# rekick2015-003.net
KiCad netlist of a schematic drawn in EAGLE
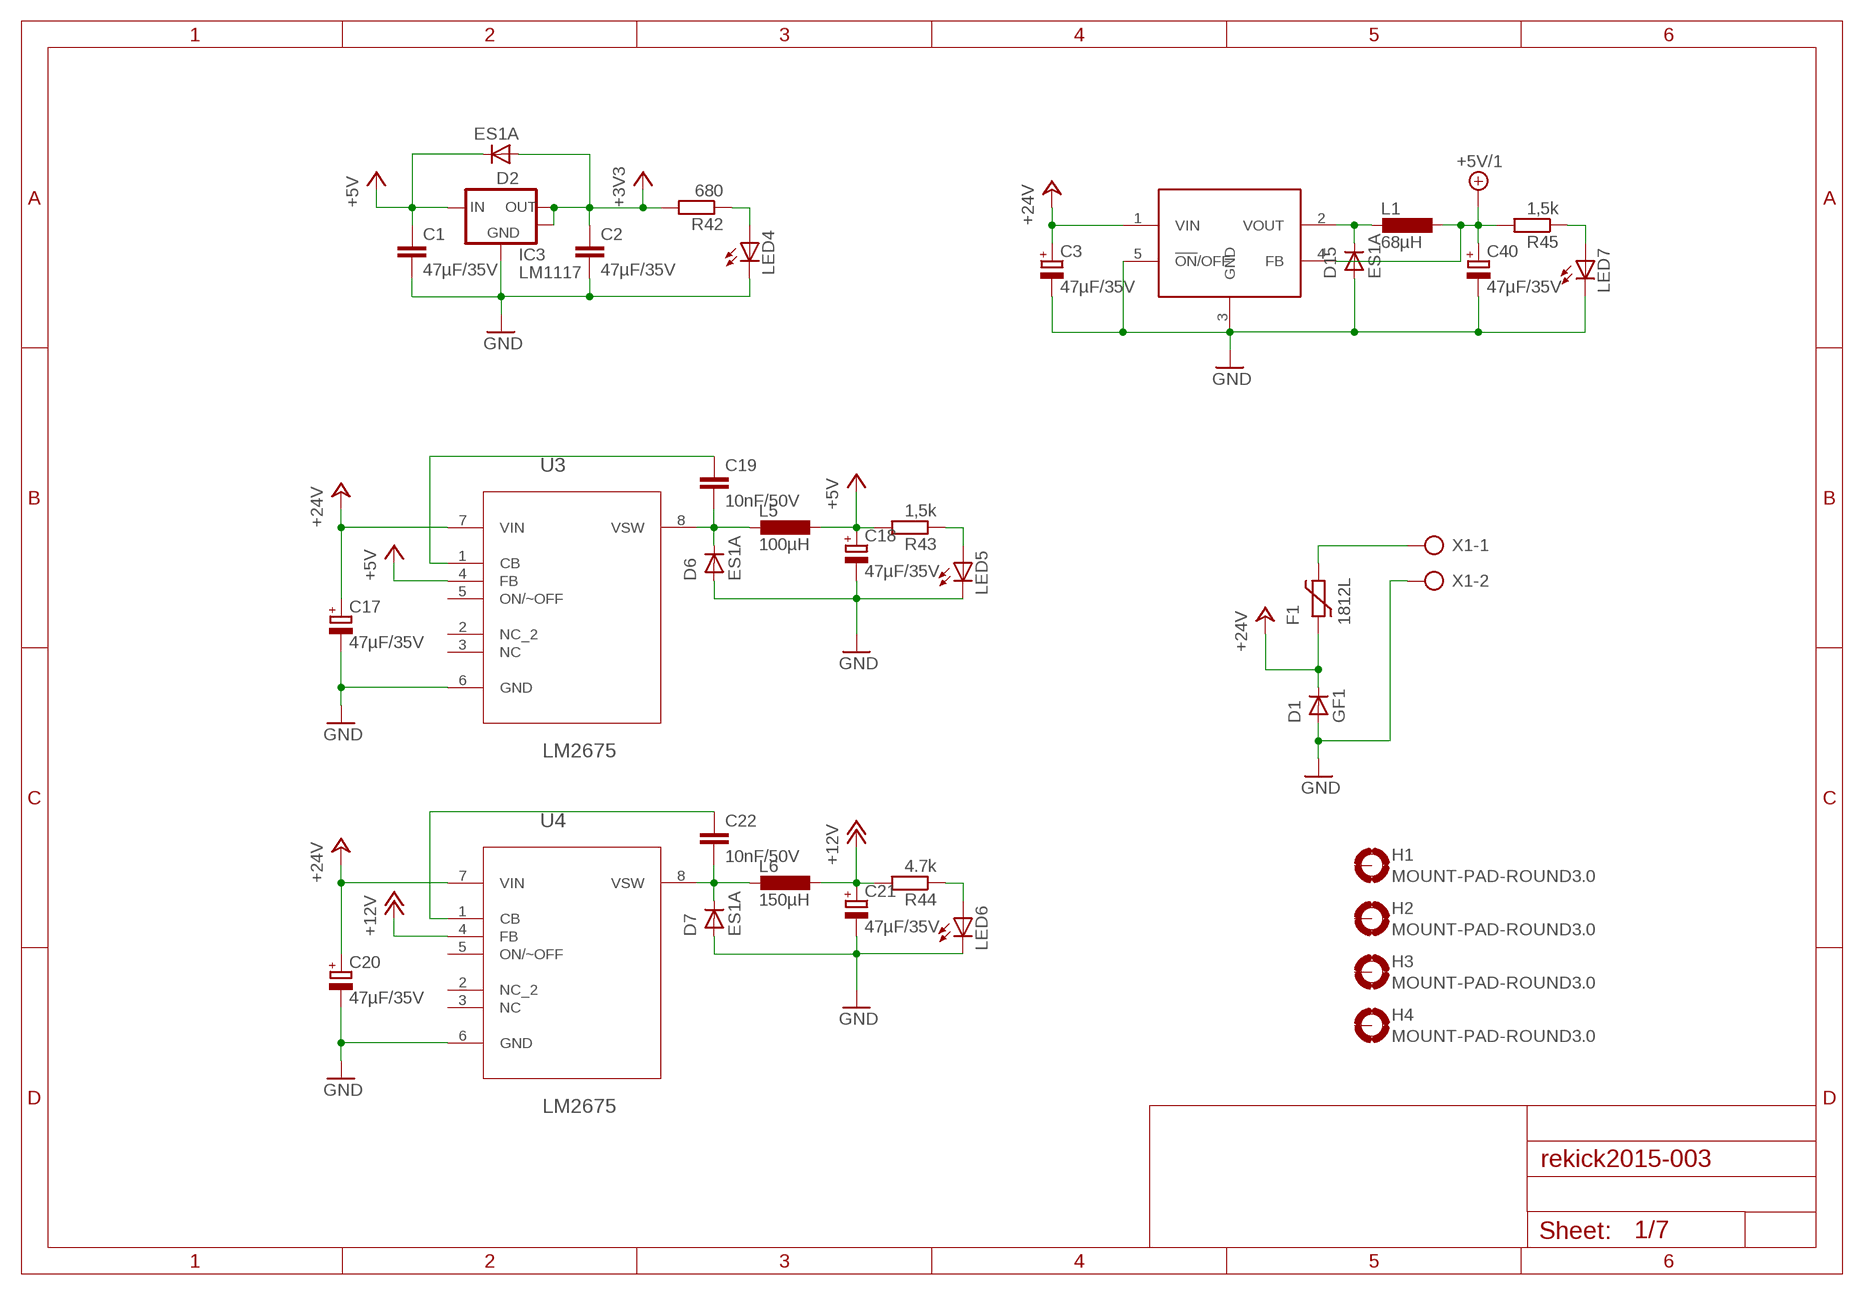
[diagram p0: schematic, sheet 1]
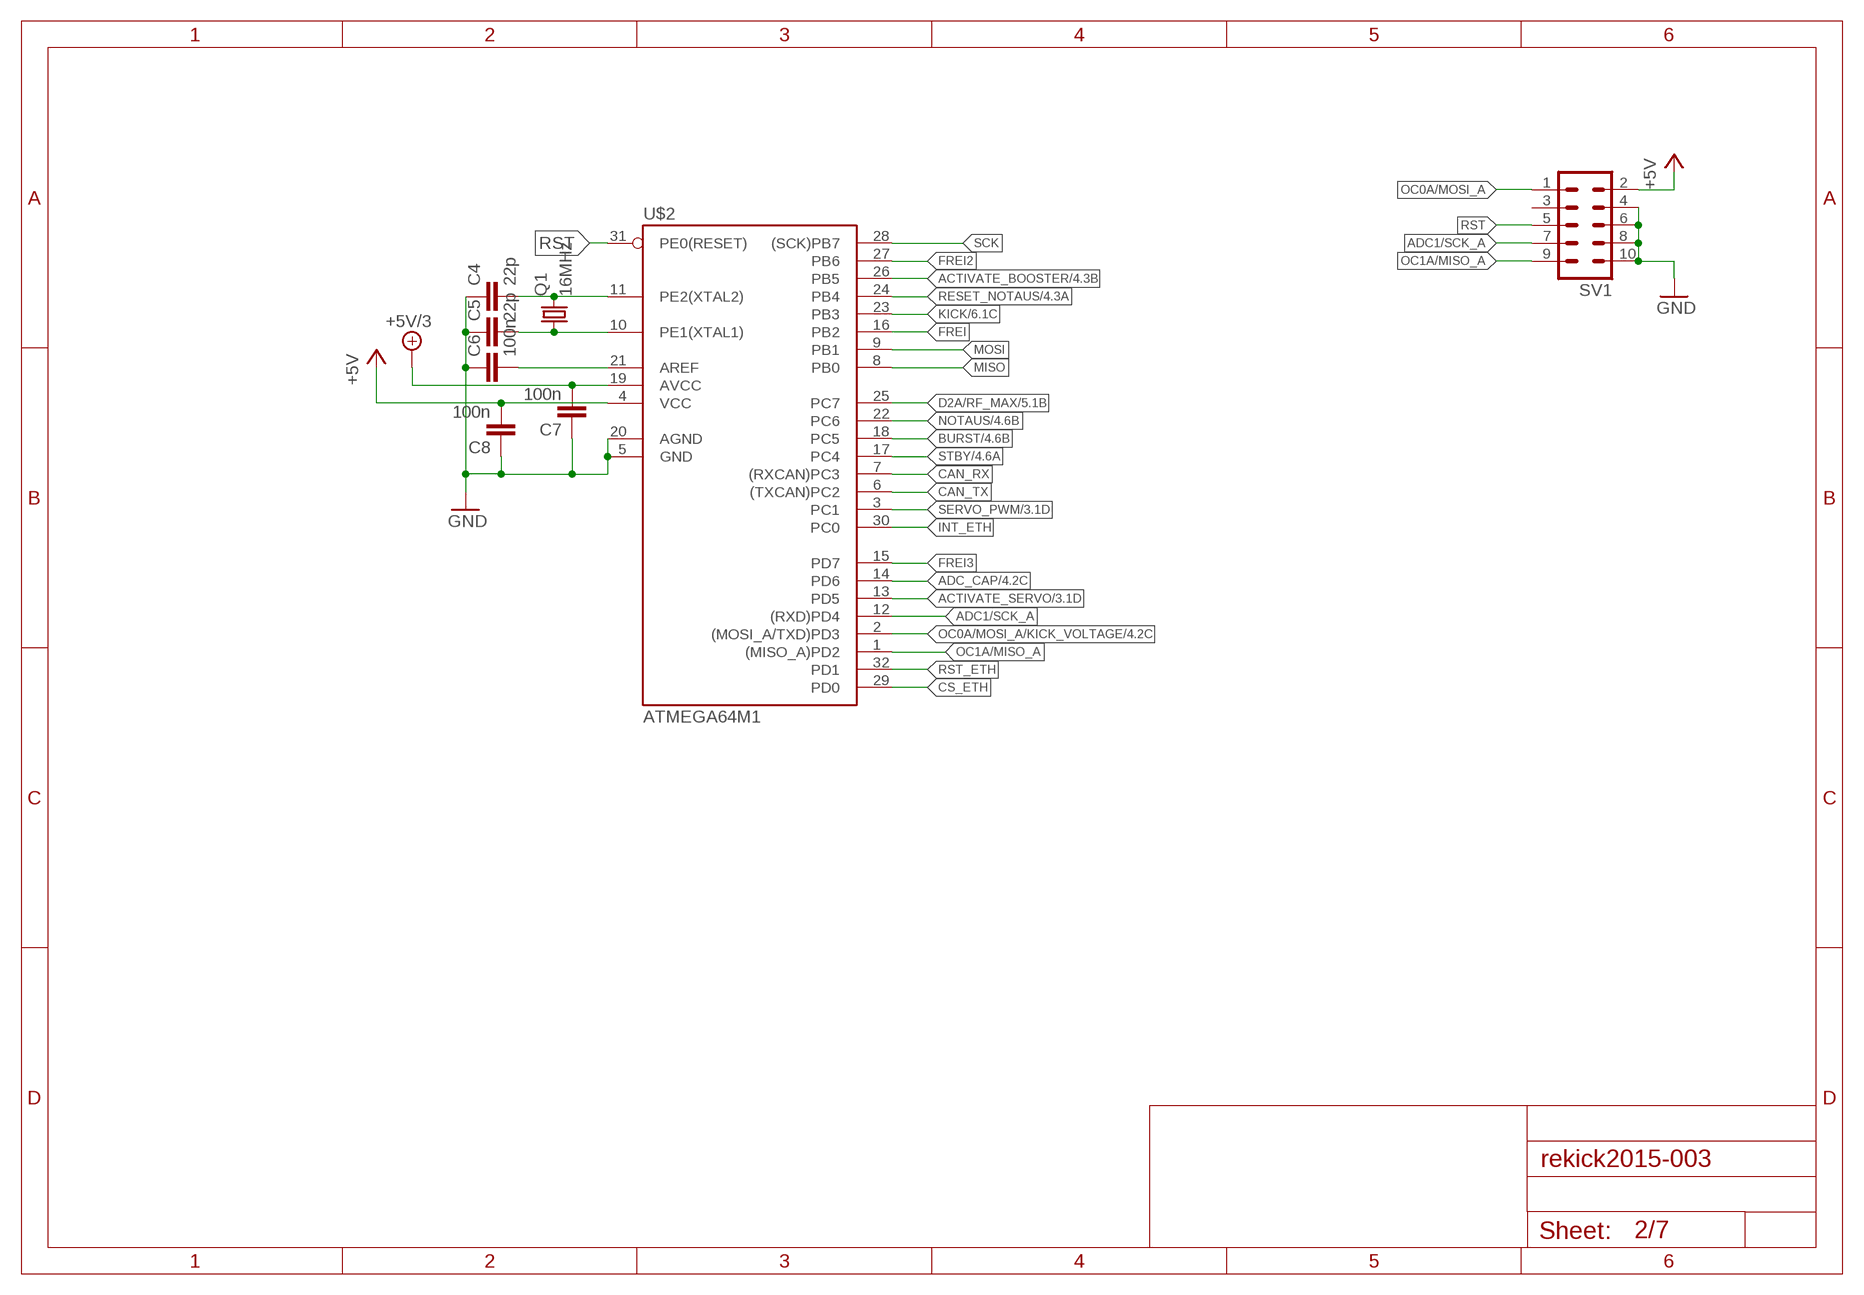
[diagram p1: schematic, sheet 2]
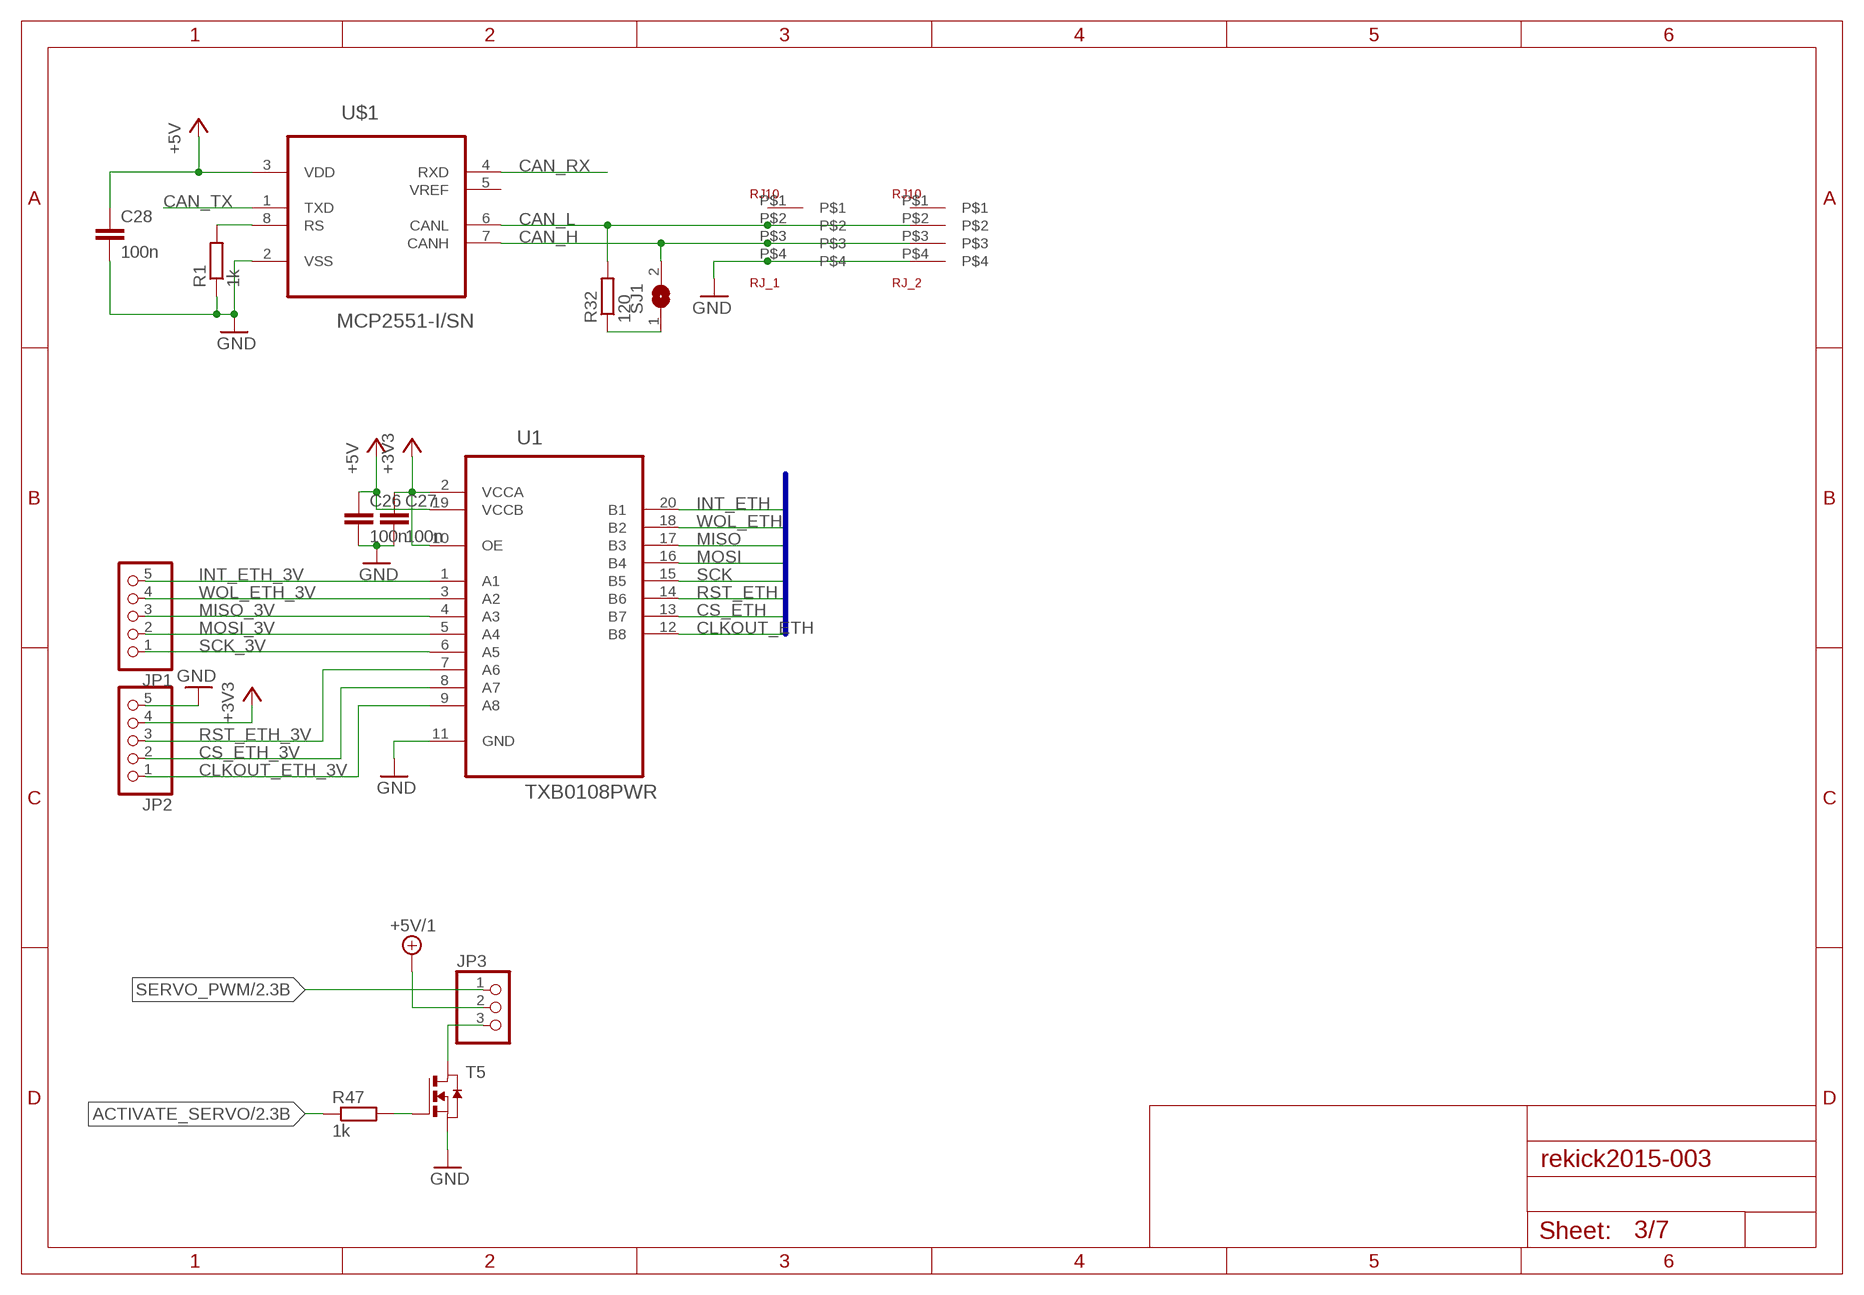
[diagram p2: schematic, sheet 3]
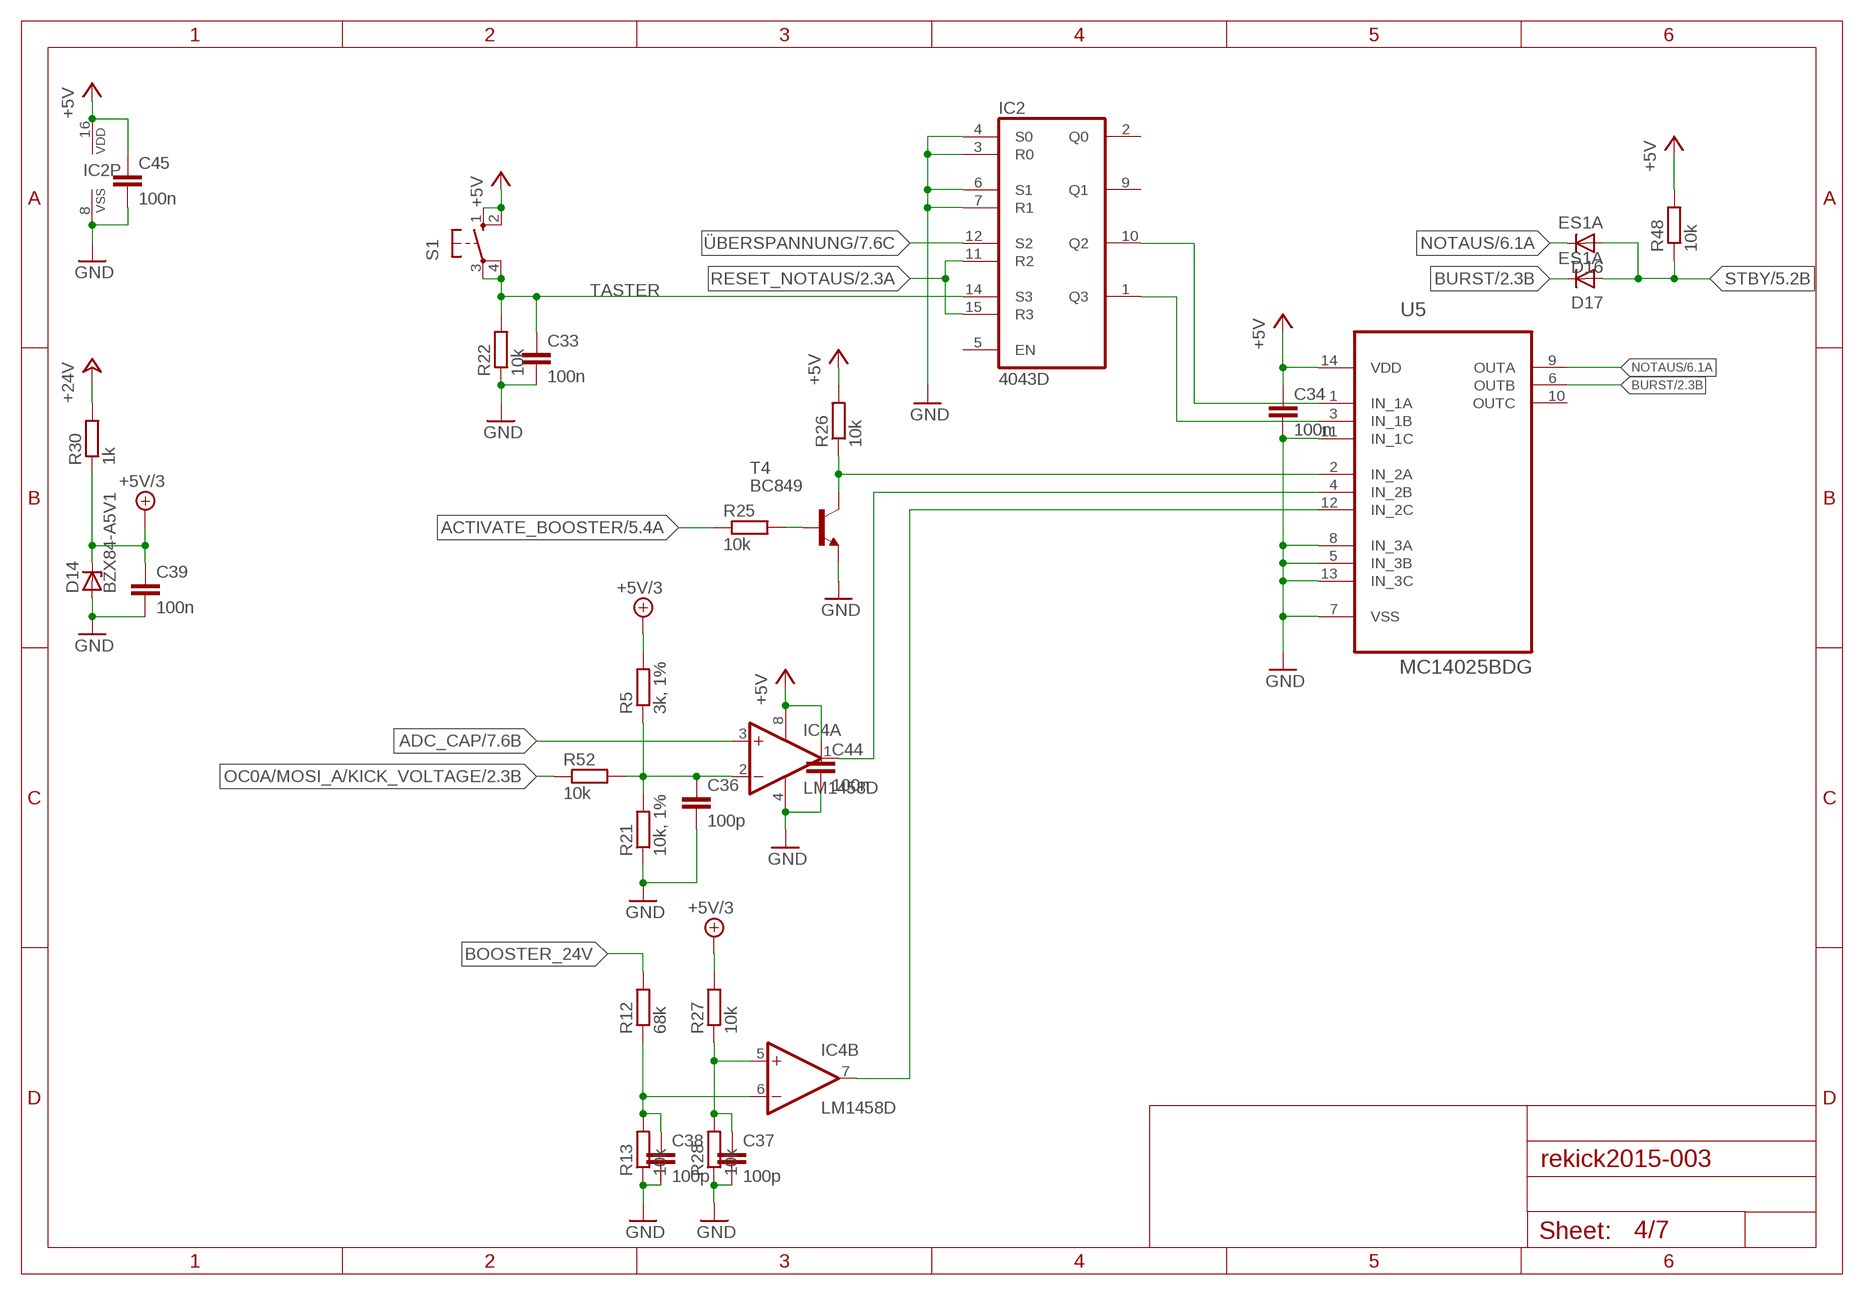
[diagram p3: schematic, sheet 4]
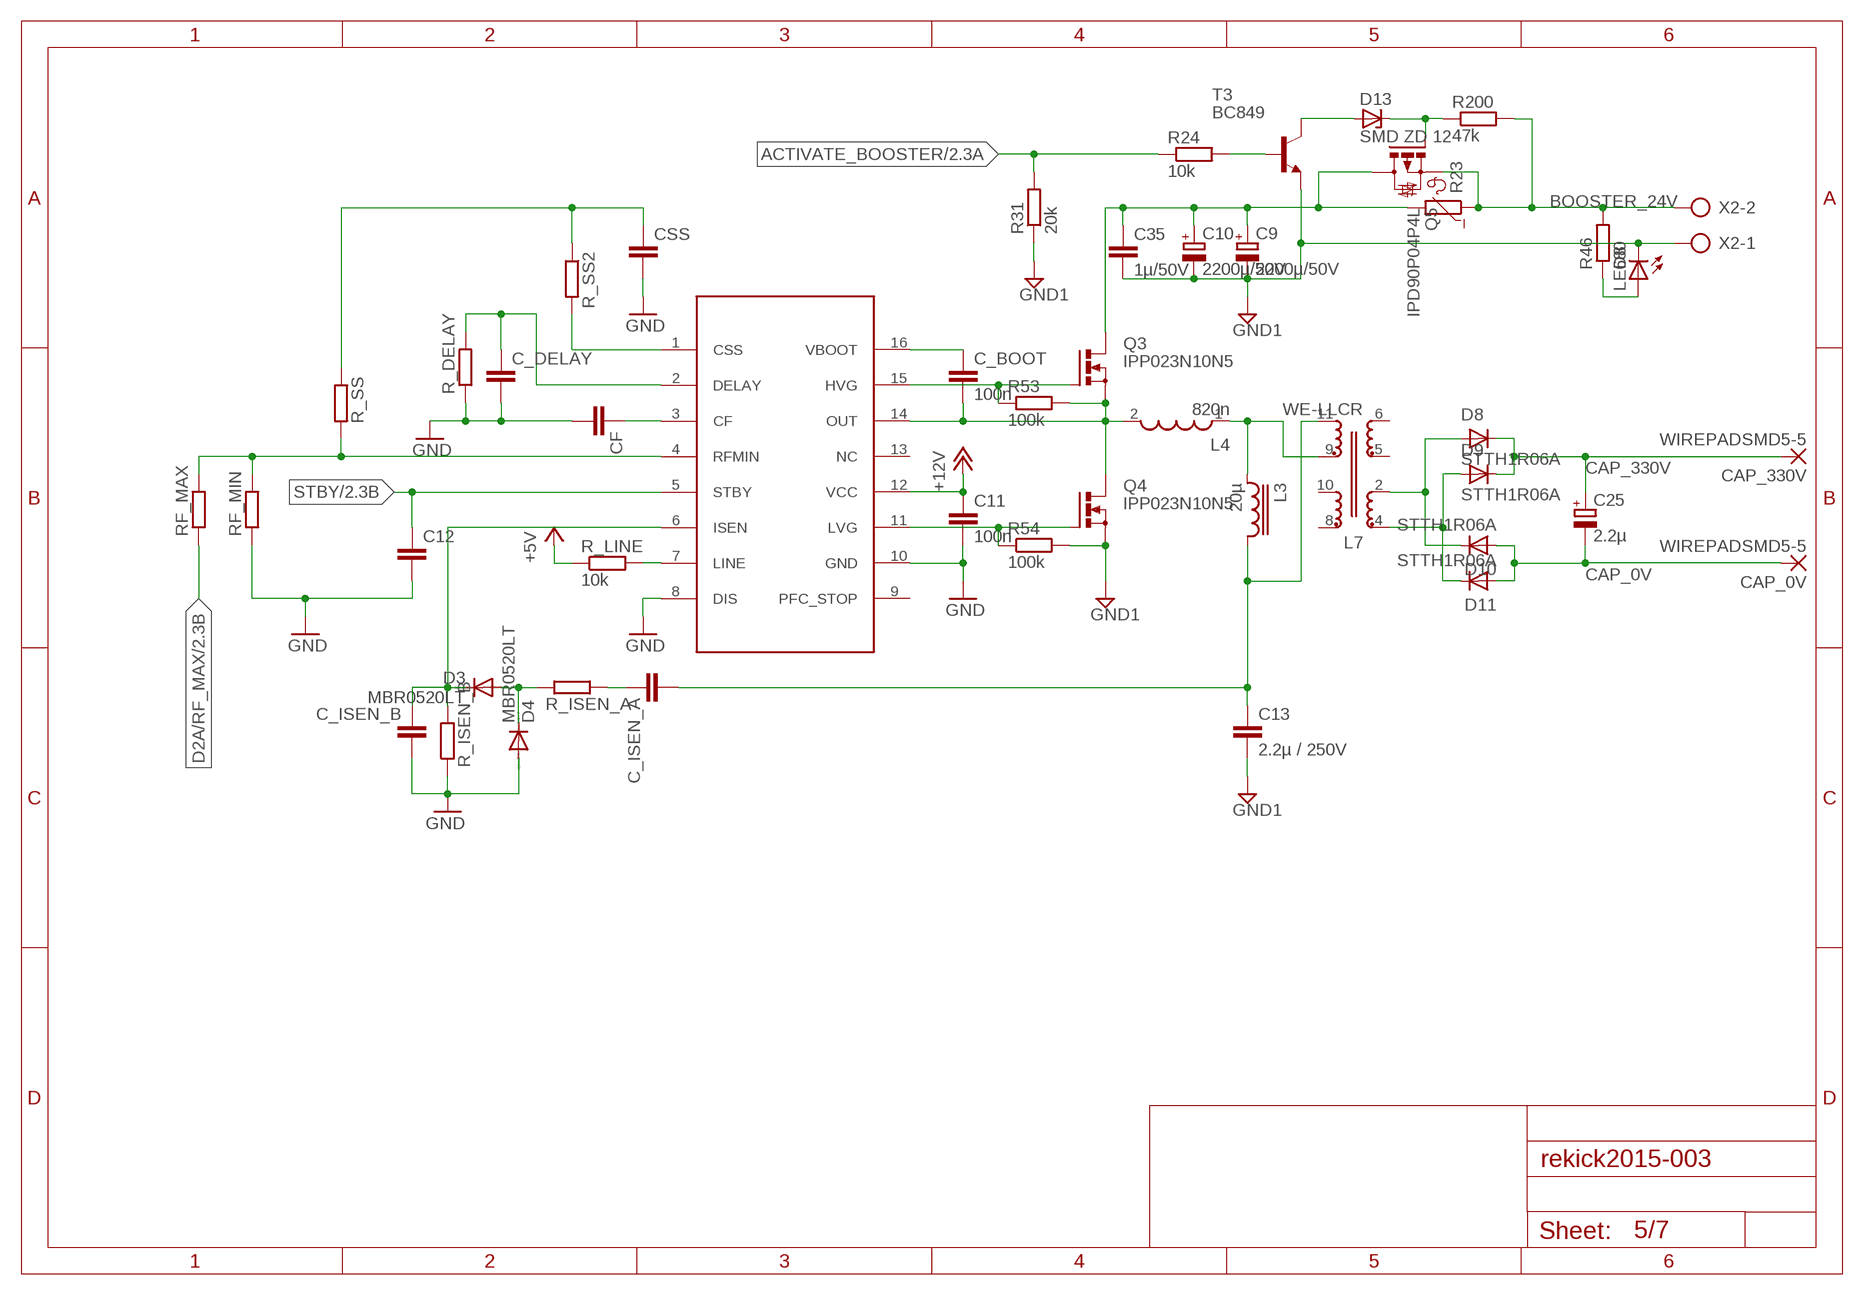
[diagram p4: schematic, sheet 5]
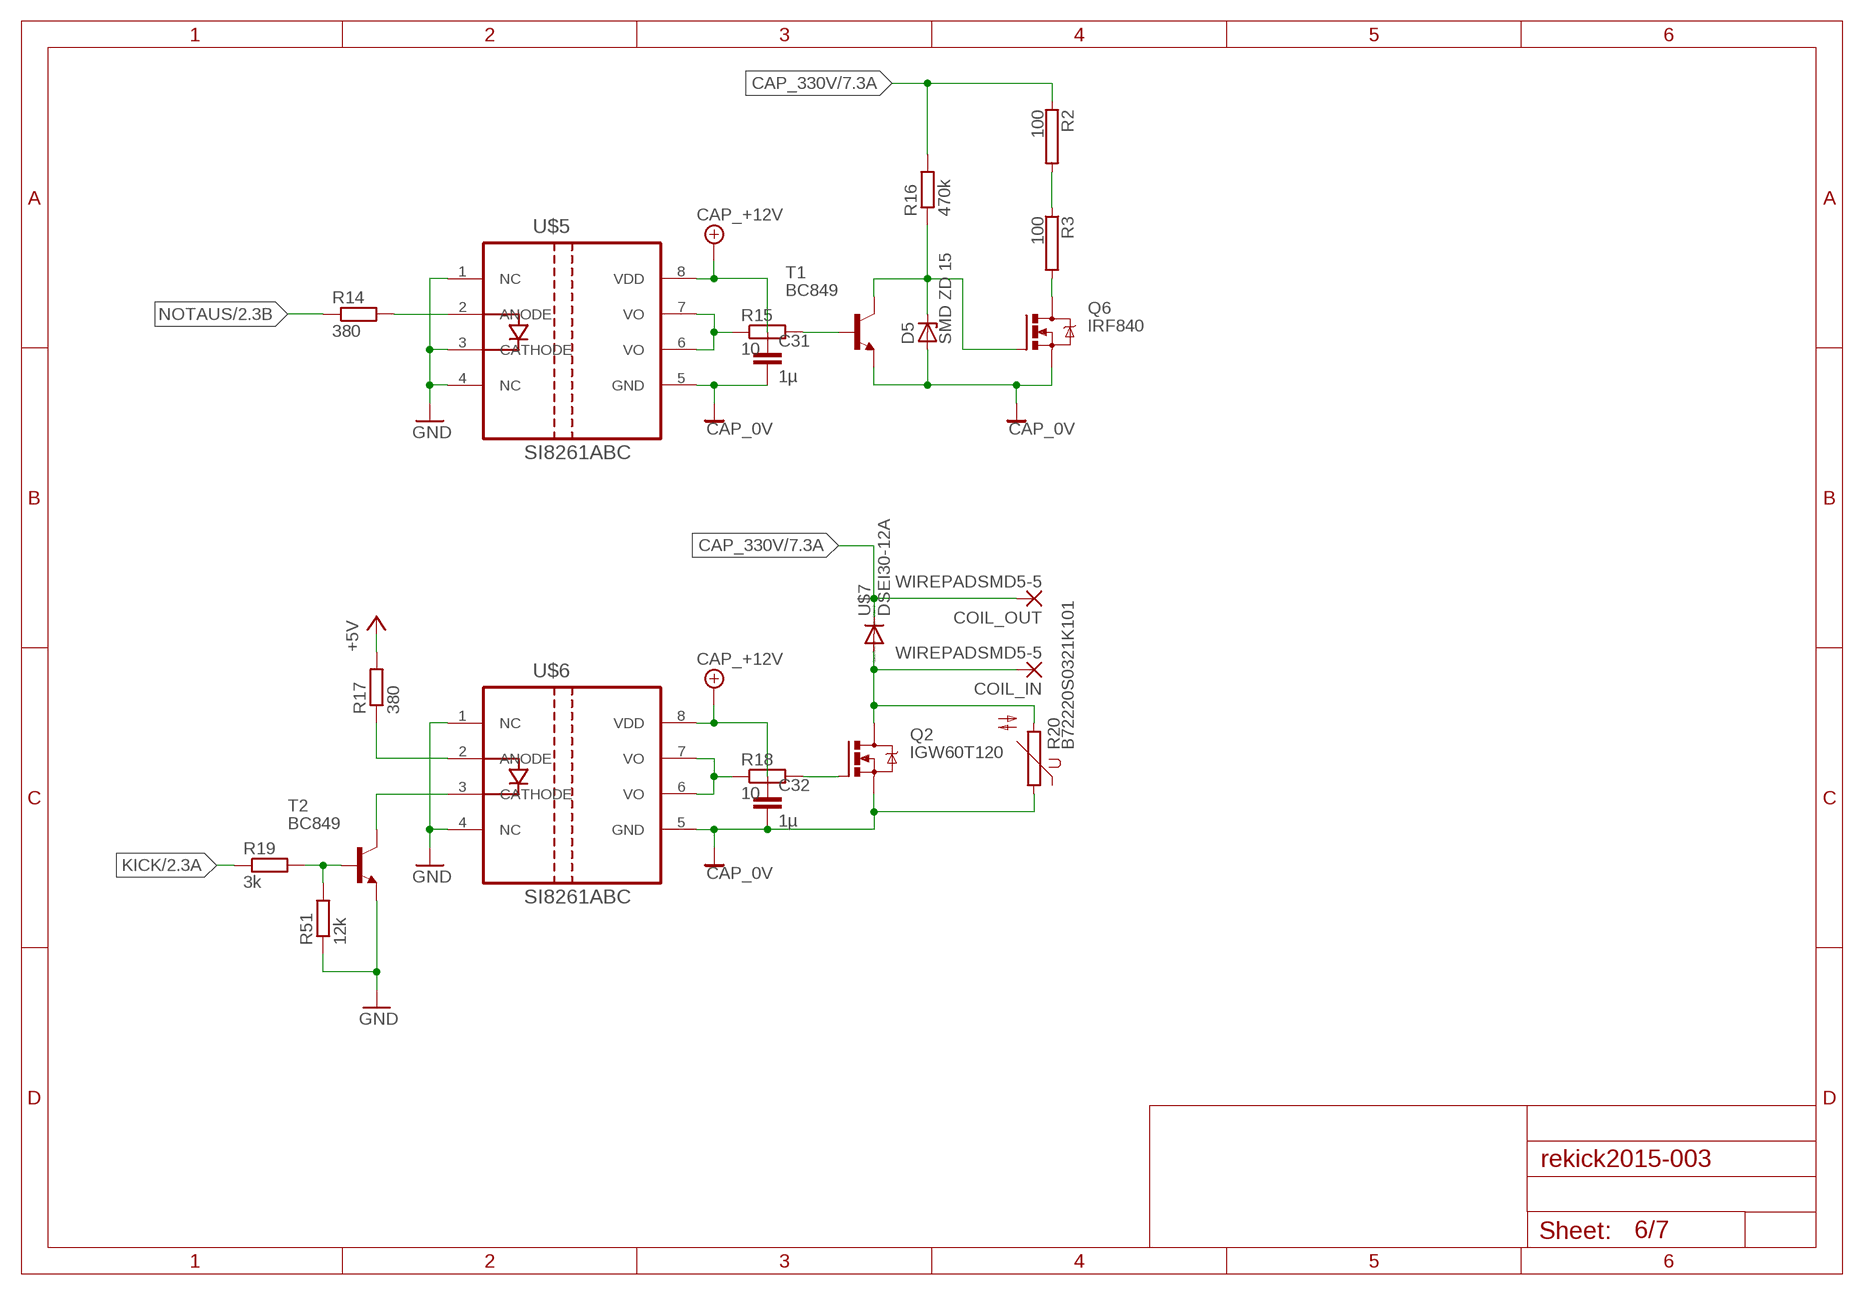
[diagram p5: schematic, sheet 6]
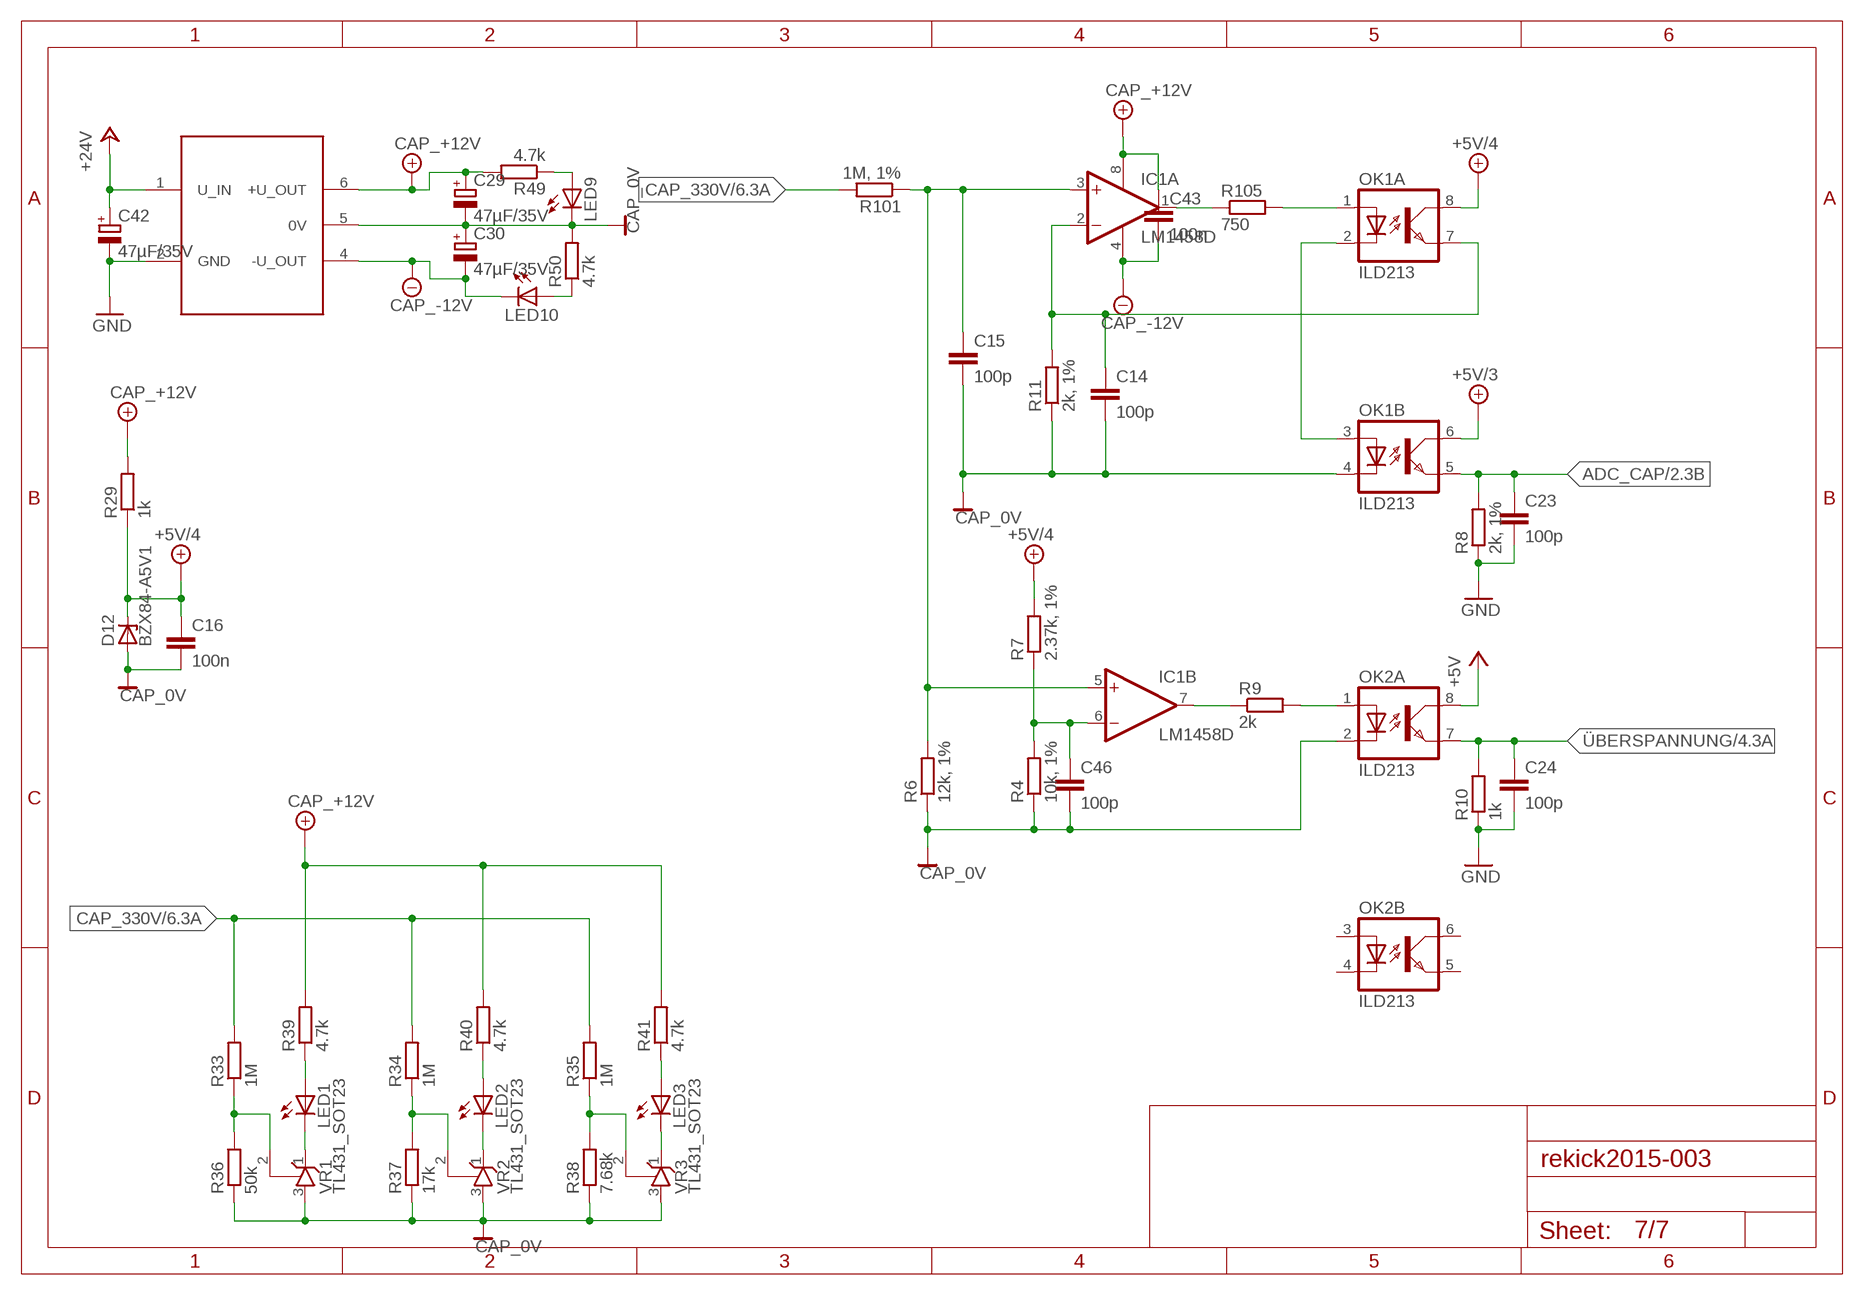
[diagram p6: schematic, sheet 7]

(export (version "E")
  (design (tool "Eeschema 10.0.6"))
  (components
    (comp (ref "C31")
      (value "1µ")
      (footprint "eagle-import:C0603")
      (libsource (lib "eagle-import") (part "C-EUC0603"))
    )
    (comp (ref "C32")
      (value "1µ")
      (footprint "eagle-import:C0603")
      (libsource (lib "eagle-import") (part "C-EUC0603"))
    )
    (comp (ref "COIL_IN")
      (value "WIREPADSMD5-5")
      (footprint "eagle-import:5-5")
      (libsource (lib "eagle-import") (part "WIREPADSMD5-5"))
    )
    (comp (ref "COIL_OUT")
      (value "WIREPADSMD5-5")
      (footprint "eagle-import:5-5")
      (libsource (lib "eagle-import") (part "WIREPADSMD5-5"))
    )
    (comp (ref "D5")
      (value "SMD ZD 15")
      (footprint "eagle-import:TO236")
      (libsource (lib "eagle-import") (part "BZX84CSMD"))
    )
    (comp (ref "Q2")
      (value "IGW60T120")
      (footprint "eagle-import:TO247BV")
      (libsource (lib "eagle-import") (part "IRFPC40"))
    )
    (comp (ref "Q6")
      (value "IRF840")
      (footprint "eagle-import:TO220BV")
      (libsource (lib "eagle-import") (part "IRF740"))
    )
    (comp (ref "R2")
      (value "100")
      (footprint "eagle-import:HS25")
      (libsource (lib "eagle-import") (part "RHS25"))
    )
    (comp (ref "R3")
      (value "100")
      (footprint "eagle-import:HS25")
      (libsource (lib "eagle-import") (part "RHS25"))
    )
    (comp (ref "R14")
      (value "380")
      (footprint "eagle-import:R0805")
      (libsource (lib "eagle-import") (part "R-EU_R0805"))
    )
    (comp (ref "R15")
      (value "10")
      (footprint "eagle-import:R0805")
      (libsource (lib "eagle-import") (part "R-EU_R0805"))
    )
    (comp (ref "R16")
      (value "470k")
      (footprint "eagle-import:0207_15")
      (libsource (lib "eagle-import") (part "R-EU_0207/15"))
    )
    (comp (ref "R17")
      (value "380")
      (footprint "eagle-import:R0805")
      (libsource (lib "eagle-import") (part "R-EU_R0805"))
    )
    (comp (ref "R18")
      (value "10")
      (footprint "eagle-import:R0805")
      (libsource (lib "eagle-import") (part "R-EU_R0805"))
    )
    (comp (ref "R19")
      (value "3k")
      (footprint "eagle-import:R0805")
      (libsource (lib "eagle-import") (part "R-EU_R0805"))
    )
    (comp (ref "R20")
      (value "B72220S0321K101")
      (footprint "eagle-import:S20K320")
      (libsource (lib "eagle-import") (part "S20K320"))
    )
    (comp (ref "R51")
      (value "12k")
      (footprint "eagle-import:R0805")
      (libsource (lib "eagle-import") (part "R-EU_R0805"))
    )
    (comp (ref "T1")
      (value "BC849")
      (footprint "eagle-import:SOT23")
      (libsource (lib "eagle-import") (part "BC849"))
    )
    (comp (ref "T2")
      (value "BC849")
      (footprint "eagle-import:SOT23")
      (libsource (lib "eagle-import") (part "BC849"))
    )
    (comp (ref "U$5")
      (value "SI8261ABC")
      (footprint "eagle-import:SOIC-8")
      (libsource (lib "eagle-import") (part "SI8261ABC"))
    )
    (comp (ref "U$6")
      (value "SI8261ABC")
      (footprint "eagle-import:SOIC-8")
      (libsource (lib "eagle-import") (part "SI8261ABC"))
    )
    (comp (ref "U$7")
      (value "DSEI30-12A")
      (footprint "eagle-import:TO247AD")
      (libsource (lib "eagle-import") (part "DSEI30-12A"))
    )
    (comp (ref "C33")
      (value "100n")
      (footprint "eagle-import:C0603")
      (libsource (lib "eagle-import") (part "C-EUC0603"))
    )
    (comp (ref "C34")
      (value "100n")
      (footprint "eagle-import:C0603")
      (libsource (lib "eagle-import") (part "C-EUC0603"))
    )
    (comp (ref "C36")
      (value "100p")
      (footprint "eagle-import:C0603")
      (libsource (lib "eagle-import") (part "C-EUC0603"))
    )
    (comp (ref "C37")
      (value "100p")
      (footprint "eagle-import:C0603")
      (libsource (lib "eagle-import") (part "C-EUC0603"))
    )
    (comp (ref "C38")
      (value "100p")
      (footprint "eagle-import:C0603")
      (libsource (lib "eagle-import") (part "C-EUC0603"))
    )
    (comp (ref "C39")
      (value "100n")
      (footprint "eagle-import:C0603")
      (libsource (lib "eagle-import") (part "C-EUC0603"))
    )
    (comp (ref "C44")
      (value "100n")
      (footprint "eagle-import:C0603")
      (libsource (lib "eagle-import") (part "C-EUC0603"))
    )
    (comp (ref "C45")
      (value "100n")
      (footprint "eagle-import:C0603")
      (libsource (lib "eagle-import") (part "C-EUC0603"))
    )
    (comp (ref "D14")
      (value "BZX84-A5V1")
      (footprint "eagle-import:TO236")
      (libsource (lib "eagle-import") (part "BZX84CSMD"))
    )
    (comp (ref "D16")
      (value "ES1A")
      (footprint "eagle-import:SMA-DO214AC")
      (libsource (lib "eagle-import") (part "GF1"))
    )
    (comp (ref "D17")
      (value "ES1A")
      (footprint "eagle-import:SMA-DO214AC")
      (libsource (lib "eagle-import") (part "GF1"))
    )
    (comp (ref "IC2")
      (value "4043D")
      (footprint "eagle-import:SO16")
      (libsource (lib "eagle-import") (part "4043D"))
    )
    (comp (ref "IC4")
      (value "LM1458D")
      (footprint "eagle-import:SO08")
      (libsource (lib "eagle-import") (part "1458DLM"))
    )
    (comp (ref "R5")
      (value "3k, 1%")
      (footprint "eagle-import:R0805")
      (libsource (lib "eagle-import") (part "R-EU_R0805"))
    )
    (comp (ref "R12")
      (value "68k")
      (footprint "eagle-import:R0805")
      (libsource (lib "eagle-import") (part "R-EU_R0805"))
    )
    (comp (ref "R13")
      (value "10k")
      (footprint "eagle-import:R0805")
      (libsource (lib "eagle-import") (part "R-EU_R0805"))
    )
    (comp (ref "R21")
      (value "10k, 1%")
      (footprint "eagle-import:R0805")
      (libsource (lib "eagle-import") (part "R-EU_R0805"))
    )
    (comp (ref "R22")
      (value "10k")
      (footprint "eagle-import:R0805")
      (libsource (lib "eagle-import") (part "R-EU_R0805"))
    )
    (comp (ref "R25")
      (value "10k")
      (footprint "eagle-import:R0805")
      (libsource (lib "eagle-import") (part "R-EU_R0805"))
    )
    (comp (ref "R26")
      (value "10k")
      (footprint "eagle-import:R0805")
      (libsource (lib "eagle-import") (part "R-EU_R0805"))
    )
    (comp (ref "R27")
      (value "10k")
      (footprint "eagle-import:R0805")
      (libsource (lib "eagle-import") (part "R-EU_R0805"))
    )
    (comp (ref "R28")
      (value "10k")
      (footprint "eagle-import:R0805")
      (libsource (lib "eagle-import") (part "R-EU_R0805"))
    )
    (comp (ref "R30")
      (value "1k")
      (footprint "eagle-import:R0805")
      (libsource (lib "eagle-import") (part "R-EU_R0805"))
    )
    (comp (ref "R48")
      (value "10k")
      (footprint "eagle-import:R0805")
      (libsource (lib "eagle-import") (part "R-EU_R0805"))
    )
    (comp (ref "R52")
      (value "10k")
      (footprint "eagle-import:R0805")
      (libsource (lib "eagle-import") (part "R-EU_R0805"))
    )
    (comp (ref "S1")
      (value "10-XX")
      (footprint "eagle-import:B3F-10XX")
      (libsource (lib "eagle-import") (part "10-XX"))
    )
    (comp (ref "T4")
      (value "BC849")
      (footprint "eagle-import:SOT23")
      (libsource (lib "eagle-import") (part "BC849"))
    )
    (comp (ref "U5")
      (value "MC14025BDG")
      (footprint "eagle-import:SOIC127P600X175-14N")
      (libsource (lib "eagle-import") (part "MC14025BDG"))
    )
    (comp (ref "C14")
      (value "100p")
      (footprint "eagle-import:C0603")
      (libsource (lib "eagle-import") (part "C-EUC0603"))
    )
    (comp (ref "C15")
      (value "100p")
      (footprint "eagle-import:C0603")
      (libsource (lib "eagle-import") (part "C-EUC0603"))
    )
    (comp (ref "C16")
      (value "100n")
      (footprint "eagle-import:C0603")
      (libsource (lib "eagle-import") (part "C-EUC0603"))
    )
    (comp (ref "C23")
      (value "100p")
      (footprint "eagle-import:C0603")
      (libsource (lib "eagle-import") (part "C-EUC0603"))
    )
    (comp (ref "C24")
      (value "100p")
      (footprint "eagle-import:C0603")
      (libsource (lib "eagle-import") (part "C-EUC0603"))
    )
    (comp (ref "C29")
      (value "47µF/35V")
      (footprint "eagle-import:PANASONIC_D")
      (libsource (lib "eagle-import") (part "CPOL-EUD"))
    )
    (comp (ref "C30")
      (value "47µF/35V")
      (footprint "eagle-import:PANASONIC_D")
      (libsource (lib "eagle-import") (part "CPOL-EUD"))
    )
    (comp (ref "C42")
      (value "47µF/35V")
      (footprint "eagle-import:PANASONIC_D")
      (libsource (lib "eagle-import") (part "CPOL-EUD"))
    )
    (comp (ref "C43")
      (value "100n")
      (footprint "eagle-import:C0603")
      (libsource (lib "eagle-import") (part "C-EUC0603"))
    )
    (comp (ref "C46")
      (value "100p")
      (footprint "eagle-import:C0603")
      (libsource (lib "eagle-import") (part "C-EUC0603"))
    )
    (comp (ref "D12")
      (value "BZX84-A5V1")
      (footprint "eagle-import:TO236")
      (libsource (lib "eagle-import") (part "BZX84CSMD"))
    )
    (comp (ref "IC1")
      (value "LM1458D")
      (footprint "eagle-import:SO08")
      (libsource (lib "eagle-import") (part "1458DLM"))
    )
    (comp (ref "LED1")
      (value "LEDCHIP-LED0805")
      (footprint "eagle-import:CHIP-LED0805")
      (libsource (lib "eagle-import") (part "LEDCHIP-LED0805"))
    )
    (comp (ref "LED2")
      (value "LEDCHIP-LED0805")
      (footprint "eagle-import:CHIP-LED0805")
      (libsource (lib "eagle-import") (part "LEDCHIP-LED0805"))
    )
    (comp (ref "LED3")
      (value "LEDCHIP-LED0805")
      (footprint "eagle-import:CHIP-LED0805")
      (libsource (lib "eagle-import") (part "LEDCHIP-LED0805"))
    )
    (comp (ref "LED9")
      (value "LEDCHIP-LED0805")
      (footprint "eagle-import:CHIP-LED0805")
      (libsource (lib "eagle-import") (part "LEDCHIP-LED0805"))
    )
    (comp (ref "LED10")
      (value "LEDCHIP-LED0805")
      (footprint "eagle-import:CHIP-LED0805")
      (libsource (lib "eagle-import") (part "LEDCHIP-LED0805"))
    )
    (comp (ref "OK1")
      (value "ILD213")
      (footprint "eagle-import:SOIC08")
      (libsource (lib "eagle-import") (part "ILD213"))
    )
    (comp (ref "OK2")
      (value "ILD213")
      (footprint "eagle-import:SOIC08")
      (libsource (lib "eagle-import") (part "ILD213"))
    )
    (comp (ref "R4")
      (value "10k, 1%")
      (footprint "eagle-import:R0805")
      (libsource (lib "eagle-import") (part "R-EU_R0805"))
    )
    (comp (ref "R6")
      (value "12k, 1%")
      (footprint "eagle-import:R0805")
      (libsource (lib "eagle-import") (part "R-EU_R0805"))
    )
    (comp (ref "R7")
      (value "2.37k, 1%")
      (footprint "eagle-import:R0805")
      (libsource (lib "eagle-import") (part "R-EU_R0805"))
    )
    (comp (ref "R8")
      (value "2k, 1%")
      (footprint "eagle-import:R0805")
      (libsource (lib "eagle-import") (part "R-EU_R0805"))
    )
    (comp (ref "R9")
      (value "2k")
      (footprint "eagle-import:R0805")
      (libsource (lib "eagle-import") (part "R-EU_R0805"))
    )
    (comp (ref "R10")
      (value "1k")
      (footprint "eagle-import:R0805")
      (libsource (lib "eagle-import") (part "R-EU_R0805"))
    )
    (comp (ref "R11")
      (value "2k, 1%")
      (footprint "eagle-import:R0805")
      (libsource (lib "eagle-import") (part "R-EU_R0805"))
    )
    (comp (ref "R29")
      (value "1k")
      (footprint "eagle-import:R0805")
      (libsource (lib "eagle-import") (part "R-EU_R0805"))
    )
    (comp (ref "R33")
      (value "1M")
      (footprint "eagle-import:R2512")
      (libsource (lib "eagle-import") (part "R-EU_R2512"))
    )
    (comp (ref "R34")
      (value "1M")
      (footprint "eagle-import:R2512")
      (libsource (lib "eagle-import") (part "R-EU_R2512"))
    )
    (comp (ref "R35")
      (value "1M")
      (footprint "eagle-import:R2512")
      (libsource (lib "eagle-import") (part "R-EU_R2512"))
    )
    (comp (ref "R36")
      (value "50k")
      (footprint "eagle-import:R0805")
      (libsource (lib "eagle-import") (part "R-EU_R0805"))
    )
    (comp (ref "R37")
      (value "17k")
      (footprint "eagle-import:R0805")
      (libsource (lib "eagle-import") (part "R-EU_R0805"))
    )
    (comp (ref "R38")
      (value "7.68k")
      (footprint "eagle-import:R0805")
      (libsource (lib "eagle-import") (part "R-EU_R0805"))
    )
    (comp (ref "R39")
      (value "4.7k")
      (footprint "eagle-import:R0805")
      (libsource (lib "eagle-import") (part "R-EU_R0805"))
    )
    (comp (ref "R40")
      (value "4.7k")
      (footprint "eagle-import:R0805")
      (libsource (lib "eagle-import") (part "R-EU_R0805"))
    )
    (comp (ref "R41")
      (value "4.7k")
      (footprint "eagle-import:R0805")
      (libsource (lib "eagle-import") (part "R-EU_R0805"))
    )
    (comp (ref "R49")
      (value "4.7k")
      (footprint "eagle-import:R0805")
      (libsource (lib "eagle-import") (part "R-EU_R0805"))
    )
    (comp (ref "R50")
      (value "4.7k")
      (footprint "eagle-import:R0805")
      (libsource (lib "eagle-import") (part "R-EU_R0805"))
    )
    (comp (ref "R101")
      (value "1M, 1%")
      (footprint "eagle-import:R2512")
      (libsource (lib "eagle-import") (part "R-EU_R2512"))
    )
    (comp (ref "R105")
      (value "750")
      (footprint "eagle-import:R0805")
      (libsource (lib "eagle-import") (part "R-EU_R0805"))
    )
    (comp (ref "U$4")
      (value "TMH-D")
      (footprint "eagle-import:TMH-D")
      (libsource (lib "eagle-import") (part "TMH-D"))
    )
    (comp (ref "VR1")
      (value "TL431_SOT23")
      (footprint "eagle-import:SOT23")
      (libsource (lib "eagle-import") (part "TL431_SOT23"))
    )
    (comp (ref "VR2")
      (value "TL431_SOT23")
      (footprint "eagle-import:SOT23")
      (libsource (lib "eagle-import") (part "TL431_SOT23"))
    )
    (comp (ref "VR3")
      (value "TL431_SOT23")
      (footprint "eagle-import:SOT23")
      (libsource (lib "eagle-import") (part "TL431_SOT23"))
    )
    (comp (ref "C1")
      (value "47µF/35V")
      (footprint "eagle-import:C0603")
      (libsource (lib "eagle-import") (part "C-EUC0603"))
    )
    (comp (ref "C2")
      (value "47µF/35V")
      (footprint "eagle-import:C0603")
      (libsource (lib "eagle-import") (part "C-EUC0603"))
    )
    (comp (ref "C3")
      (value "47µF/35V")
      (footprint "eagle-import:PANASONIC_D")
      (libsource (lib "eagle-import") (part "CPOL-EUD"))
    )
    (comp (ref "C17")
      (value "47µF/35V")
      (footprint "eagle-import:PANASONIC_D")
      (libsource (lib "eagle-import") (part "CPOL-EUD"))
    )
    (comp (ref "C18")
      (value "47µF/35V")
      (footprint "eagle-import:PANASONIC_D")
      (libsource (lib "eagle-import") (part "CPOL-EUD"))
    )
    (comp (ref "C19")
      (value "10nF/50V")
      (footprint "eagle-import:C0603")
      (libsource (lib "eagle-import") (part "C-EUC0603"))
    )
    (comp (ref "C20")
      (value "47µF/35V")
      (footprint "eagle-import:PANASONIC_D")
      (libsource (lib "eagle-import") (part "CPOL-EUD"))
    )
    (comp (ref "C21")
      (value "47µF/35V")
      (footprint "eagle-import:PANASONIC_D")
      (libsource (lib "eagle-import") (part "CPOL-EUD"))
    )
    (comp (ref "C22")
      (value "10nF/50V")
      (footprint "eagle-import:C0603")
      (libsource (lib "eagle-import") (part "C-EUC0603"))
    )
    (comp (ref "C40")
      (value "47µF/35V")
      (footprint "eagle-import:PANASONIC_D")
      (libsource (lib "eagle-import") (part "CPOL-EUD"))
    )
    (comp (ref "D1")
      (value "GF1")
      (footprint "eagle-import:SMA-DO214AC")
      (libsource (lib "eagle-import") (part "GF1"))
    )
    (comp (ref "D2")
      (value "ES1A")
      (footprint "eagle-import:SMA-DO214AC")
      (libsource (lib "eagle-import") (part "GF1"))
    )
    (comp (ref "D6")
      (value "ES1A")
      (footprint "eagle-import:SMA-DO214AC")
      (libsource (lib "eagle-import") (part "GF1"))
    )
    (comp (ref "D7")
      (value "ES1A")
      (footprint "eagle-import:SMA-DO214AC")
      (libsource (lib "eagle-import") (part "GF1"))
    )
    (comp (ref "D15")
      (value "ES1A")
      (footprint "eagle-import:SMA-DO214AC")
      (libsource (lib "eagle-import") (part "GF1"))
    )
    (comp (ref "F1")
      (value "1812L")
      (footprint "eagle-import:1812L")
      (libsource (lib "eagle-import") (part "1812L"))
    )
    (comp (ref "H1")
      (value "MOUNT-PAD-ROUND3.0")
      (footprint "eagle-import:3,0-PAD")
      (libsource (lib "eagle-import") (part "MOUNT-PAD-ROUND3.0"))
    )
    (comp (ref "H2")
      (value "MOUNT-PAD-ROUND3.0")
      (footprint "eagle-import:3,0-PAD")
      (libsource (lib "eagle-import") (part "MOUNT-PAD-ROUND3.0"))
    )
    (comp (ref "H3")
      (value "MOUNT-PAD-ROUND3.0")
      (footprint "eagle-import:3,0-PAD")
      (libsource (lib "eagle-import") (part "MOUNT-PAD-ROUND3.0"))
    )
    (comp (ref "H4")
      (value "MOUNT-PAD-ROUND3.0")
      (footprint "eagle-import:3,0-PAD")
      (libsource (lib "eagle-import") (part "MOUNT-PAD-ROUND3.0"))
    )
    (comp (ref "IC3")
      (value "LM1117")
      (footprint "eagle-import:SOT223")
      (libsource (lib "eagle-import") (part "LM1117"))
    )
    (comp (ref "L1")
      (value "68µH")
      (footprint "eagle-import:PISM")
      (libsource (lib "eagle-import") (part "L-EUPISM"))
    )
    (comp (ref "L5")
      (value "100µH")
      (footprint "eagle-import:PISM")
      (libsource (lib "eagle-import") (part "L-EUPISM"))
    )
    (comp (ref "L6")
      (value "150µH")
      (footprint "eagle-import:PISM")
      (libsource (lib "eagle-import") (part "L-EUPISM"))
    )
    (comp (ref "LED4")
      (value "LEDCHIP-LED0805")
      (footprint "eagle-import:CHIP-LED0805")
      (libsource (lib "eagle-import") (part "LEDCHIP-LED0805"))
    )
    (comp (ref "LED5")
      (value "LEDCHIP-LED0805")
      (footprint "eagle-import:CHIP-LED0805")
      (libsource (lib "eagle-import") (part "LEDCHIP-LED0805"))
    )
    (comp (ref "LED6")
      (value "LEDCHIP-LED0805")
      (footprint "eagle-import:CHIP-LED0805")
      (libsource (lib "eagle-import") (part "LEDCHIP-LED0805"))
    )
    (comp (ref "LED7")
      (value "LEDCHIP-LED0805")
      (footprint "eagle-import:CHIP-LED0805")
      (libsource (lib "eagle-import") (part "LEDCHIP-LED0805"))
    )
    (comp (ref "R42")
      (value "680")
      (footprint "eagle-import:R0805")
      (libsource (lib "eagle-import") (part "R-EU_R0805"))
    )
    (comp (ref "R43")
      (value "1,5k")
      (footprint "eagle-import:R0805")
      (libsource (lib "eagle-import") (part "R-EU_R0805"))
    )
    (comp (ref "R44")
      (value "4.7k")
      (footprint "eagle-import:R0805")
      (libsource (lib "eagle-import") (part "R-EU_R0805"))
    )
    (comp (ref "R45")
      (value "1,5k")
      (footprint "eagle-import:R0805")
      (libsource (lib "eagle-import") (part "R-EU_R0805"))
    )
    (comp (ref "U$8")
      (value "LM2576")
      (footprint "eagle-import:TO220511")
      (libsource (lib "eagle-import") (part "LM2576"))
    )
    (comp (ref "U3")
      (value "LM2675")
      (footprint "eagle-import:SOIC127P620X175-8N")
      (fields (field (name "MPN") "LM2675M-3.3"))
      (libsource (lib "eagle-import") (part "LM2675M-3.3"))
    )
    (comp (ref "U4")
      (value "LM2675")
      (footprint "eagle-import:SOIC127P620X175-8N")
      (fields (field (name "MPN") "LM2675M-3.3"))
      (libsource (lib "eagle-import") (part "LM2675M-3.3"))
    )
    (comp (ref "X1")
      (value "AK500/2-H")
      (footprint "eagle-import:AK500_2-H")
      (libsource (lib "eagle-import") (part "AK500/2-H"))
    )
    (comp (ref "C9")
      (value "2200µ/50V")
      (footprint "eagle-import:E5-13")
      (libsource (lib "eagle-import") (part "CPOL-EUE5-13"))
    )
    (comp (ref "C10")
      (value "2200µ/50V")
      (footprint "eagle-import:E5-13")
      (libsource (lib "eagle-import") (part "CPOL-EUE5-13"))
    )
    (comp (ref "C11")
      (value "100n")
      (footprint "eagle-import:C0603")
      (libsource (lib "eagle-import") (part "C-EUC0603"))
    )
    (comp (ref "C12")
      (value "C-EUC0603")
      (footprint "eagle-import:C0603")
      (libsource (lib "eagle-import") (part "C-EUC0603"))
    )
    (comp (ref "C13")
      (value "2.2µ / 250V")
      (footprint "eagle-import:C2220K")
      (libsource (lib "eagle-import") (part "C-EUC2220K"))
    )
    (comp (ref "C25")
      (value "2.2µ")
      (footprint "eagle-import:E5-10,5")
      (libsource (lib "eagle-import") (part "CPOL-EUE5-10.5"))
    )
    (comp (ref "C35")
      (value "1µ/50V")
      (footprint "eagle-import:C0603")
      (libsource (lib "eagle-import") (part "C-EUC0603"))
    )
    (comp (ref "CAP_0V")
      (value "WIREPADSMD5-5")
      (footprint "eagle-import:5-5")
      (libsource (lib "eagle-import") (part "WIREPADSMD5-5"))
    )
    (comp (ref "CAP_330V")
      (value "WIREPADSMD5-5")
      (footprint "eagle-import:5-5")
      (libsource (lib "eagle-import") (part "WIREPADSMD5-5"))
    )
    (comp (ref "CF")
      (value "C-EUC0603")
      (footprint "eagle-import:C0603")
      (libsource (lib "eagle-import") (part "C-EUC0603"))
    )
    (comp (ref "CSS")
      (value "C-EUC0603")
      (footprint "eagle-import:C0603")
      (libsource (lib "eagle-import") (part "C-EUC0603"))
    )
    (comp (ref "C_BOOT")
      (value "100n")
      (footprint "eagle-import:C0603")
      (libsource (lib "eagle-import") (part "C-EUC0603"))
    )
    (comp (ref "C_DELAY")
      (value "C-EUC0603")
      (footprint "eagle-import:C0603")
      (libsource (lib "eagle-import") (part "C-EUC0603"))
    )
    (comp (ref "C_ISEN_A")
      (value "C-EUC0603")
      (footprint "eagle-import:C0603")
      (libsource (lib "eagle-import") (part "C-EUC0603"))
    )
    (comp (ref "C_ISEN_B")
      (value "C-EUC0603")
      (footprint "eagle-import:C0603")
      (libsource (lib "eagle-import") (part "C-EUC0603"))
    )
    (comp (ref "D3")
      (value "MBR0520LT")
      (footprint "eagle-import:SOD123")
      (libsource (lib "eagle-import") (part "MBR0520LT"))
    )
    (comp (ref "D4")
      (value "MBR0520LT")
      (footprint "eagle-import:SOD123")
      (libsource (lib "eagle-import") (part "MBR0520LT"))
    )
    (comp (ref "D8")
      (value "STTH1R06A")
      (footprint "eagle-import:SMA-DO214AC")
      (libsource (lib "eagle-import") (part "GF1"))
    )
    (comp (ref "D9")
      (value "STTH1R06A")
      (footprint "eagle-import:SMA-DO214AC")
      (libsource (lib "eagle-import") (part "GF1"))
    )
    (comp (ref "D10")
      (value "STTH1R06A")
      (footprint "eagle-import:SMA-DO214AC")
      (libsource (lib "eagle-import") (part "GF1"))
    )
    (comp (ref "D11")
      (value "STTH1R06A")
      (footprint "eagle-import:SMA-DO214AC")
      (libsource (lib "eagle-import") (part "GF1"))
    )
    (comp (ref "D13")
      (value "SMD ZD 12")
      (footprint "eagle-import:TO236")
      (libsource (lib "eagle-import") (part "BZX84CSMD"))
    )
    (comp (ref "L3")
      (value "20µ")
      (footprint "eagle-import:SRR1210")
      (libsource (lib "eagle-import") (part "SRR1210"))
    )
    (comp (ref "L4")
      (value "820n")
      (footprint "eagle-import:WE-HCI_1890")
      (libsource (lib "eagle-import") (part "WE-HCI_1890"))
    )
    (comp (ref "L7")
      (value "WE-LLCR")
      (footprint "eagle-import:WE-LLCR_ETD34")
      (libsource (lib "eagle-import") (part "WE-LLCR_ETD34"))
    )
    (comp (ref "LED8")
      (value "LEDCHIP-LED0805")
      (footprint "eagle-import:CHIP-LED0805")
      (libsource (lib "eagle-import") (part "LEDCHIP-LED0805"))
    )
    (comp (ref "Q3")
      (value "IPP023N10N5")
      (footprint "eagle-import:TO220BV")
      (libsource (lib "eagle-import") (part "PMOSFET_NTO220BV"))
    )
    (comp (ref "Q4")
      (value "IPP023N10N5")
      (footprint "eagle-import:TO220BV")
      (libsource (lib "eagle-import") (part "PMOSFET_NTO220BV"))
    )
    (comp (ref "Q5")
      (value "IPD90P04P4L")
      (footprint "eagle-import:D-PAK_TO252AA")
      (libsource (lib "eagle-import") (part "IRF?5305R"))
    )
    (comp (ref "R23")
      (value "NTC644A")
      (footprint "eagle-import:N644A")
      (libsource (lib "eagle-import") (part "NTC644A"))
    )
    (comp (ref "R24")
      (value "10k")
      (footprint "eagle-import:R0805")
      (libsource (lib "eagle-import") (part "R-EU_R0805"))
    )
    (comp (ref "R31")
      (value "20k")
      (footprint "eagle-import:R0805")
      (libsource (lib "eagle-import") (part "R-EU_R0805"))
    )
    (comp (ref "R46")
      (value "680")
      (footprint "eagle-import:R0805")
      (libsource (lib "eagle-import") (part "R-EU_R0805"))
    )
    (comp (ref "R53")
      (value "100k")
      (footprint "eagle-import:R0805")
      (libsource (lib "eagle-import") (part "R-EU_R0805"))
    )
    (comp (ref "R54")
      (value "100k")
      (footprint "eagle-import:R0805")
      (libsource (lib "eagle-import") (part "R-EU_R0805"))
    )
    (comp (ref "R200")
      (value "47k")
      (footprint "eagle-import:R0805")
      (libsource (lib "eagle-import") (part "R-EU_R0805"))
    )
    (comp (ref "RF_MAX")
      (value "R-EU_R0805")
      (footprint "eagle-import:R0805")
      (libsource (lib "eagle-import") (part "R-EU_R0805"))
    )
    (comp (ref "RF_MIN")
      (value "R-EU_R0805")
      (footprint "eagle-import:R0805")
      (libsource (lib "eagle-import") (part "R-EU_R0805"))
    )
    (comp (ref "R_DELAY")
      (value "R-EU_R0805")
      (footprint "eagle-import:R0805")
      (libsource (lib "eagle-import") (part "R-EU_R0805"))
    )
    (comp (ref "R_ISEN_A")
      (value "R-EU_R0805")
      (footprint "eagle-import:R0805")
      (libsource (lib "eagle-import") (part "R-EU_R0805"))
    )
    (comp (ref "R_ISEN_B")
      (value "R-EU_R0805")
      (footprint "eagle-import:R0805")
      (libsource (lib "eagle-import") (part "R-EU_R0805"))
    )
    (comp (ref "R_LINE")
      (value "10k")
      (footprint "eagle-import:R0805")
      (libsource (lib "eagle-import") (part "R-EU_R0805"))
    )
    (comp (ref "R_SS")
      (value "R-EU_R0805")
      (footprint "eagle-import:R0805")
      (libsource (lib "eagle-import") (part "R-EU_R0805"))
    )
    (comp (ref "R_SS2")
      (value "R-EU_R0805")
      (footprint "eagle-import:R0805")
      (libsource (lib "eagle-import") (part "R-EU_R0805"))
    )
    (comp (ref "T3")
      (value "BC849")
      (footprint "eagle-import:SOT23")
      (libsource (lib "eagle-import") (part "BC849"))
    )
    (comp (ref "U$3")
      (value "L6599")
      (footprint "eagle-import:SO16")
      (libsource (lib "eagle-import") (part "L6599"))
    )
    (comp (ref "X2")
      (value "AK500/2-H")
      (footprint "eagle-import:AK500_2-H")
      (libsource (lib "eagle-import") (part "AK500/2-H"))
    )
    (comp (ref "C4")
      (value "22p")
      (footprint "eagle-import:C0603")
      (libsource (lib "eagle-import") (part "C-EUC0603"))
    )
    (comp (ref "C5")
      (value "22p")
      (footprint "eagle-import:C0603")
      (libsource (lib "eagle-import") (part "C-EUC0603"))
    )
    (comp (ref "C6")
      (value "100n")
      (footprint "eagle-import:C0603")
      (libsource (lib "eagle-import") (part "C-EUC0603"))
    )
    (comp (ref "C7")
      (value "100n")
      (footprint "eagle-import:C0603")
      (libsource (lib "eagle-import") (part "C-EUC0603"))
    )
    (comp (ref "C8")
      (value "100n")
      (footprint "eagle-import:C0603")
      (libsource (lib "eagle-import") (part "C-EUC0603"))
    )
    (comp (ref "Q1")
      (value "16MHz")
      (footprint "eagle-import:HC49UP")
      (libsource (lib "eagle-import") (part "CRYSTALHC49UP"))
    )
    (comp (ref "SV1")
      (value "ML10")
      (footprint "eagle-import:ML10")
      (libsource (lib "eagle-import") (part "ML10"))
    )
    (comp (ref "U$2")
      (value "ATMEGA64M1")
      (footprint "eagle-import:TQFP32-08")
      (libsource (lib "eagle-import") (part "ATMEGA64M1"))
    )
    (comp (ref "C26")
      (value "100n")
      (footprint "eagle-import:C0603")
      (libsource (lib "eagle-import") (part "C-EUC0603"))
    )
    (comp (ref "C27")
      (value "100n")
      (footprint "eagle-import:C0603")
      (libsource (lib "eagle-import") (part "C-EUC0603"))
    )
    (comp (ref "C28")
      (value "100n")
      (footprint "eagle-import:C0603")
      (libsource (lib "eagle-import") (part "C-EUC0603"))
    )
    (comp (ref "JP1")
      (value "PINHD-1X5")
      (footprint "eagle-import:1X05")
      (libsource (lib "eagle-import") (part "PINHD-1X5"))
    )
    (comp (ref "JP2")
      (value "PINHD-1X5")
      (footprint "eagle-import:1X05")
      (libsource (lib "eagle-import") (part "PINHD-1X5"))
    )
    (comp (ref "JP3")
      (value "PINHD-1X3")
      (footprint "eagle-import:1X03")
      (libsource (lib "eagle-import") (part "PINHD-1X3"))
    )
    (comp (ref "R1")
      (value "1k")
      (footprint "eagle-import:R0805")
      (libsource (lib "eagle-import") (part "R-EU_R0805"))
    )
    (comp (ref "R32")
      (value "120")
      (footprint "eagle-import:R0805")
      (libsource (lib "eagle-import") (part "R-EU_R0805"))
    )
    (comp (ref "R47")
      (value "1k")
      (footprint "eagle-import:R0805")
      (libsource (lib "eagle-import") (part "R-EU_R0805"))
    )
    (comp (ref "RJ_1")
      (value "RJ10")
      (footprint "eagle-import:RJ10")
      (libsource (lib "eagle-import") (part "RJ10"))
    )
    (comp (ref "RJ_2")
      (value "RJ10")
      (footprint "eagle-import:RJ10")
      (libsource (lib "eagle-import") (part "RJ10"))
    )
    (comp (ref "SJ1") (value "SJ") (footprint "eagle-import:SJ") (libsource (lib "eagle-import") (part "SJ")))
    (comp (ref "T5")
      (value "NMOSSOT23")
      (footprint "eagle-import:SOT-23")
      (libsource (lib "eagle-import") (part "NMOSSOT23"))
    )
    (comp (ref "U$1")
      (value "MCP2551-I/SN")
      (footprint "eagle-import:SOIC127P600X175-8N")
      (libsource (lib "eagle-import") (part "MCP2551-I/SN"))
    )
    (comp (ref "U1")
      (value "TXB0108PWR")
      (footprint "eagle-import:SOP65P640X120-20N")
      (libsource (lib "eagle-import") (part "TXB0108PWR"))
    )
  )
  (nets
    (net (code "1") (name "+3V3") (class "Default")
      (node (ref "C2") (pin "1") (pinfunction "1_1") (pintype "passive"))
      (node (ref "C27") (pin "1") (pinfunction "1_1") (pintype "passive"))
      (node (ref "D2") (pin "A") (pinfunction "A_A") (pintype "passive"))
      (node (ref "IC3") (pin "2") (pinfunction "OUT_2") (pintype "passive"))
      (node (ref "IC3") (pin "4") (pinfunction "OUT_4") (pintype "input"))
      (node (ref "JP2") (pin "4") (pinfunction "4_4") (pintype "passive"))
      (node (ref "R42") (pin "2") (pinfunction "2_2") (pintype "passive"))
      (node (ref "U1") (pin "10") (pinfunction "OE_10") (pintype "input"))
      (node (ref "U1") (pin "2") (pinfunction "VCCA_2") (pintype "power_in"))
    )
    (net (code "2") (name "+5V") (class "Default")
      (node (ref "C1") (pin "1") (pinfunction "1_1") (pintype "passive"))
      (node (ref "C18") (pin "+") (pinfunction "+_+") (pintype "passive"))
      (node (ref "C26") (pin "1") (pinfunction "1_1") (pintype "passive"))
      (node (ref "C28") (pin "1") (pinfunction "1_1") (pintype "passive"))
      (node (ref "C34") (pin "1") (pinfunction "1_1") (pintype "passive"))
      (node (ref "C44") (pin "1") (pinfunction "1_1") (pintype "passive"))
      (node (ref "C45") (pin "1") (pinfunction "1_1") (pintype "passive"))
      (node (ref "C8") (pin "2") (pinfunction "2_2") (pintype "passive"))
      (node (ref "D2") (pin "K") (pinfunction "C_K") (pintype "passive"))
      (node (ref "IC2") (pin "16") (pinfunction "VDD_16") (pintype "power_in"))
      (node (ref "IC3") (pin "3") (pinfunction "IN_3") (pintype "input"))
      (node (ref "IC4") (pin "8") (pinfunction "V+_8") (pintype "power_in"))
      (node (ref "L5") (pin "1") (pinfunction "1_1") (pintype "passive"))
      (node (ref "OK2") (pin "8") (pinfunction "COL_8") (pintype "passive"))
      (node (ref "R17") (pin "2") (pinfunction "2_2") (pintype "passive"))
      (node (ref "R26") (pin "2") (pinfunction "2_2") (pintype "passive"))
      (node (ref "R43") (pin "2") (pinfunction "2_2") (pintype "passive"))
      (node (ref "R48") (pin "2") (pinfunction "2_2") (pintype "passive"))
      (node (ref "R_LINE") (pin "1") (pinfunction "1_1") (pintype "passive"))
      (node (ref "S1") (pin "1") (pinfunction "S_1") (pintype "passive"))
      (node (ref "S1") (pin "2") (pinfunction "S1_2") (pintype "passive"))
      (node (ref "SV1") (pin "2") (pinfunction "2_2") (pintype "passive"))
      (node (ref "U$1") (pin "3") (pinfunction "VDD_3") (pintype "power_in"))
      (node (ref "U$2") (pin "4") (pinfunction "VCC_4") (pintype "bidirectional"))
      (node (ref "U1") (pin "19") (pinfunction "VCCB_19") (pintype "power_in"))
      (node (ref "U3") (pin "4") (pinfunction "FB_4") (pintype "input"))
      (node (ref "U5") (pin "14") (pinfunction "VDD_14") (pintype "power_in"))
    )
    (net (code "3") (name "+5V{slash}1") (class "Default")
      (node (ref "C40") (pin "+") (pinfunction "+_+") (pintype "passive"))
      (node (ref "JP3") (pin "2") (pinfunction "2_2") (pintype "passive"))
      (node (ref "L1") (pin "1") (pinfunction "1_1") (pintype "passive"))
      (node (ref "R45") (pin "2") (pinfunction "2_2") (pintype "passive"))
      (node (ref "U$8") (pin "4") (pinfunction "FB_4") (pintype "bidirectional"))
    )
    (net (code "4") (name "+5V{slash}3") (class "Default")
      (node (ref "C39") (pin "1") (pinfunction "1_1") (pintype "passive"))
      (node (ref "C7") (pin "2") (pinfunction "2_2") (pintype "passive"))
      (node (ref "D14") (pin "C") (pinfunction "C_C") (pintype "passive"))
      (node (ref "OK1") (pin "6") (pinfunction "COL_6") (pintype "passive"))
      (node (ref "R27") (pin "2") (pinfunction "2_2") (pintype "passive"))
      (node (ref "R30") (pin "1") (pinfunction "1_1") (pintype "passive"))
      (node (ref "R5") (pin "2") (pinfunction "2_2") (pintype "passive"))
      (node (ref "U$2") (pin "19") (pinfunction "AVCC_19") (pintype "bidirectional"))
    )
    (net (code "5") (name "+5V{slash}4") (class "Default")
      (node (ref "C16") (pin "1") (pinfunction "1_1") (pintype "passive"))
      (node (ref "D12") (pin "C") (pinfunction "C_C") (pintype "passive"))
      (node (ref "OK1") (pin "8") (pinfunction "COL_8") (pintype "passive"))
      (node (ref "R29") (pin "1") (pinfunction "1_1") (pintype "passive"))
      (node (ref "R7") (pin "2") (pinfunction "2_2") (pintype "passive"))
    )
    (net (code "6") (name "+12V") (class "Default")
      (node (ref "C11") (pin "1") (pinfunction "1_1") (pintype "passive"))
      (node (ref "C21") (pin "+") (pinfunction "+_+") (pintype "passive"))
      (node (ref "L6") (pin "1") (pinfunction "1_1") (pintype "passive"))
      (node (ref "R44") (pin "2") (pinfunction "2_2") (pintype "passive"))
      (node (ref "U$3") (pin "12") (pinfunction "VCC_12") (pintype "bidirectional"))
      (node (ref "U4") (pin "4") (pinfunction "FB_4") (pintype "input"))
    )
    (net (code "7") (name "+24V") (class "Default")
      (node (ref "C17") (pin "+") (pinfunction "+_+") (pintype "passive"))
      (node (ref "C20") (pin "+") (pinfunction "+_+") (pintype "passive"))
      (node (ref "C3") (pin "+") (pinfunction "+_+") (pintype "passive"))
      (node (ref "C42") (pin "+") (pinfunction "+_+") (pintype "passive"))
      (node (ref "D1") (pin "K") (pinfunction "C_K") (pintype "passive"))
      (node (ref "F1") (pin "P$1") (pinfunction "1_P$1") (pintype "passive"))
      (node (ref "R30") (pin "2") (pinfunction "2_2") (pintype "passive"))
      (node (ref "U$4") (pin "1") (pinfunction "U_IN_1") (pintype "bidirectional"))
      (node (ref "U$8") (pin "1") (pinfunction "VIN_1") (pintype "bidirectional"))
      (node (ref "U3") (pin "7") (pinfunction "VIN_7") (pintype "power_in"))
      (node (ref "U4") (pin "7") (pinfunction "VIN_7") (pintype "power_in"))
    )
    (net (code "8") (name "ACTIVATE_BOOSTER") (class "Default")
      (node (ref "R24") (pin "1") (pinfunction "1_1") (pintype "passive"))
      (node (ref "R25") (pin "1") (pinfunction "1_1") (pintype "passive"))
      (node (ref "R31") (pin "2") (pinfunction "2_2") (pintype "passive"))
      (node (ref "U$2") (pin "26") (pinfunction "PB5_26") (pintype "bidirectional"))
    )
    (net (code "9") (name "ACTIVATE_SERVO") (class "Default")
      (node (ref "R47") (pin "1") (pinfunction "1_1") (pintype "passive"))
      (node (ref "U$2") (pin "13") (pinfunction "PD5_13") (pintype "bidirectional"))
    )
    (net (code "10") (name "ADC1{slash}SCK_A") (class "Default")
      (node (ref "SV1") (pin "7") (pinfunction "7_7") (pintype "passive"))
      (node (ref "U$2") (pin "12") (pinfunction "(RXD)PD4_12") (pintype "bidirectional"))
    )
    (net (code "11") (name "ADC_CAP") (class "Default")
      (node (ref "C23") (pin "1") (pinfunction "1_1") (pintype "passive"))
      (node (ref "IC4") (pin "3") (pinfunction "+IN_3") (pintype "input"))
      (node (ref "OK1") (pin "5") (pinfunction "EMIT_5") (pintype "passive"))
      (node (ref "R8") (pin "2") (pinfunction "2_2") (pintype "passive"))
      (node (ref "U$2") (pin "14") (pinfunction "PD6_14") (pintype "bidirectional"))
    )
    (net (code "12") (name "BOOSTER_24V") (class "Default")
      (node (ref "Q5") (pin "3") (pinfunction "S_3") (pintype "passive"))
      (node (ref "R12") (pin "2") (pinfunction "2_2") (pintype "passive"))
      (node (ref "R200") (pin "2") (pinfunction "2_2") (pintype "passive"))
      (node (ref "R23") (pin "1") (pinfunction "1_1") (pintype "passive"))
      (node (ref "R46") (pin "2") (pinfunction "2_2") (pintype "passive"))
      (node (ref "X2") (pin "2") (pinfunction "KL_2") (pintype "passive"))
    )
    (net (code "13") (name "BURST") (class "Default")
      (node (ref "D17") (pin "K") (pinfunction "C_K") (pintype "passive"))
      (node (ref "U$2") (pin "18") (pinfunction "PC5_18") (pintype "bidirectional"))
      (node (ref "U5") (pin "6") (pinfunction "OUTB_6") (pintype "output"))
    )
    (net (code "14") (name "CAN_H") (class "Default")
      (node (ref "RJ_1") (pin "P$3") (pinfunction "P$3_P$3") (pintype "bidirectional"))
      (node (ref "RJ_2") (pin "P$3") (pinfunction "P$3_P$3") (pintype "bidirectional"))
      (node (ref "SJ1") (pin "2") (pinfunction "2_2") (pintype "passive"))
      (node (ref "U$1") (pin "7") (pinfunction "CANH_7") (pintype "bidirectional"))
    )
    (net (code "15") (name "CAN_L") (class "Default")
      (node (ref "R32") (pin "2") (pinfunction "2_2") (pintype "passive"))
      (node (ref "RJ_1") (pin "P$2") (pinfunction "P$2_P$2") (pintype "bidirectional"))
      (node (ref "RJ_2") (pin "P$2") (pinfunction "P$2_P$2") (pintype "bidirectional"))
      (node (ref "U$1") (pin "6") (pinfunction "CANL_6") (pintype "bidirectional"))
    )
    (net (code "16") (name "CAN_RX") (class "Default")
      (node (ref "U$1") (pin "4") (pinfunction "RXD_4") (pintype "output"))
      (node (ref "U$2") (pin "7") (pinfunction "(RXCAN)PC3_7") (pintype "bidirectional"))
    )
    (net (code "17") (name "CAN_TX") (class "Default")
      (node (ref "U$1") (pin "1") (pinfunction "TXD_1") (pintype "input"))
      (node (ref "U$2") (pin "6") (pinfunction "(TXCAN)PC2_6") (pintype "bidirectional"))
    )
    (net (code "18") (name "CAP_+12V") (class "Default")
      (node (ref "C29") (pin "+") (pinfunction "+_+") (pintype "passive"))
      (node (ref "C31") (pin "1") (pinfunction "1_1") (pintype "passive"))
      (node (ref "C32") (pin "1") (pinfunction "1_1") (pintype "passive"))
      (node (ref "C43") (pin "1") (pinfunction "1_1") (pintype "passive"))
      (node (ref "IC1") (pin "8") (pinfunction "V+_8") (pintype "power_in"))
      (node (ref "R29") (pin "2") (pinfunction "2_2") (pintype "passive"))
      (node (ref "R39") (pin "2") (pinfunction "2_2") (pintype "passive"))
      (node (ref "R40") (pin "2") (pinfunction "2_2") (pintype "passive"))
      (node (ref "R41") (pin "2") (pinfunction "2_2") (pintype "passive"))
      (node (ref "R49") (pin "2") (pinfunction "2_2") (pintype "passive"))
      (node (ref "U$4") (pin "6") (pinfunction "+U_OUT_6") (pintype "bidirectional"))
      (node (ref "U$5") (pin "8") (pinfunction "VDD_8") (pintype "bidirectional"))
      (node (ref "U$6") (pin "8") (pinfunction "VDD_8") (pintype "bidirectional"))
    )
    (net (code "19") (name "CAP_-12V") (class "Default")
      (node (ref "C30") (pin "-") (pinfunction "-_-") (pintype "passive"))
      (node (ref "C43") (pin "2") (pinfunction "2_2") (pintype "passive"))
      (node (ref "IC1") (pin "4") (pinfunction "V-_4") (pintype "power_in"))
      (node (ref "LED10") (pin "C") (pinfunction "C_C") (pintype "passive"))
      (node (ref "U$4") (pin "4") (pinfunction "-U_OUT_4") (pintype "bidirectional"))
    )
    (net (code "20") (name "CAP_0V") (class "Default")
      (node (ref "C14") (pin "2") (pinfunction "2_2") (pintype "passive"))
      (node (ref "C15") (pin "2") (pinfunction "2_2") (pintype "passive"))
      (node (ref "C16") (pin "2") (pinfunction "2_2") (pintype "passive"))
      (node (ref "C25") (pin "-") (pinfunction "-_-") (pintype "passive"))
      (node (ref "C29") (pin "-") (pinfunction "-_-") (pintype "passive"))
      (node (ref "C30") (pin "+") (pinfunction "+_+") (pintype "passive"))
      (node (ref "C31") (pin "2") (pinfunction "2_2") (pintype "passive"))
      (node (ref "C32") (pin "2") (pinfunction "2_2") (pintype "passive"))
      (node (ref "C46") (pin "2") (pinfunction "2_2") (pintype "passive"))
      (node (ref "CAP_0V") (pin "P$1") (pinfunction "P_P$1") (pintype "passive"))
      (node (ref "D10") (pin "A") (pinfunction "A_A") (pintype "passive"))
      (node (ref "D11") (pin "A") (pinfunction "A_A") (pintype "passive"))
      (node (ref "D12") (pin "A") (pinfunction "A_A") (pintype "passive"))
      (node (ref "D5") (pin "A") (pinfunction "A_A") (pintype "passive"))
      (node (ref "LED9") (pin "C") (pinfunction "C_C") (pintype "passive"))
      (node (ref "OK1") (pin "4") (pinfunction "C_4") (pintype "passive"))
      (node (ref "OK2") (pin "2") (pinfunction "C_2") (pintype "passive"))
      (node (ref "Q2") (pin "S") (pinfunction "S_S") (pintype "passive"))
      (node (ref "Q6") (pin "S") (pinfunction "S_S") (pintype "passive"))
      (node (ref "R11") (pin "1") (pinfunction "1_1") (pintype "passive"))
      (node (ref "R20") (pin "1") (pinfunction "1_1") (pintype "passive"))
      (node (ref "R36") (pin "1") (pinfunction "1_1") (pintype "passive"))
      (node (ref "R37") (pin "1") (pinfunction "1_1") (pintype "passive"))
      (node (ref "R38") (pin "1") (pinfunction "1_1") (pintype "passive"))
      (node (ref "R4") (pin "1") (pinfunction "1_1") (pintype "passive"))
      (node (ref "R50") (pin "2") (pinfunction "2_2") (pintype "passive"))
      (node (ref "R6") (pin "1") (pinfunction "1_1") (pintype "passive"))
      (node (ref "T1") (pin "2") (pinfunction "E_2") (pintype "passive"))
      (node (ref "U$4") (pin "5") (pinfunction "0V_5") (pintype "bidirectional"))
      (node (ref "U$5") (pin "5") (pinfunction "GND_5") (pintype "bidirectional"))
      (node (ref "U$6") (pin "5") (pinfunction "GND_5") (pintype "bidirectional"))
      (node (ref "VR1") (pin "3") (pinfunction "A_3") (pintype "passive"))
      (node (ref "VR2") (pin "3") (pinfunction "A_3") (pintype "passive"))
      (node (ref "VR3") (pin "3") (pinfunction "A_3") (pintype "passive"))
    )
    (net (code "21") (name "CAP_330V") (class "Default")
      (node (ref "C25") (pin "+") (pinfunction "+_+") (pintype "passive"))
      (node (ref "CAP_330V") (pin "P$1") (pinfunction "P_P$1") (pintype "passive"))
      (node (ref "COIL_OUT") (pin "P$1") (pinfunction "P_P$1") (pintype "passive"))
      (node (ref "D8") (pin "K") (pinfunction "C_K") (pintype "passive"))
      (node (ref "D9") (pin "K") (pinfunction "C_K") (pintype "passive"))
      (node (ref "R101") (pin "2") (pinfunction "2_2") (pintype "passive"))
      (node (ref "R16") (pin "2") (pinfunction "2_2") (pintype "passive"))
      (node (ref "R2") (pin "1") (pinfunction "1_1") (pintype "passive"))
      (node (ref "R33") (pin "2") (pinfunction "2_2") (pintype "passive"))
      (node (ref "R34") (pin "2") (pinfunction "2_2") (pintype "passive"))
      (node (ref "R35") (pin "2") (pinfunction "2_2") (pintype "passive"))
      (node (ref "U$7") (pin "C") (pinfunction "C_C") (pintype "passive"))
    )
    (net (code "22") (name "CLKOUT_ETH") (class "Default")
      (node (ref "U1") (pin "12") (pinfunction "B8_12") (pintype "bidirectional"))
    )
    (net (code "23") (name "CLKOUT_ETH_3V") (class "Default")
      (node (ref "JP2") (pin "1") (pinfunction "1_1") (pintype "passive"))
      (node (ref "U1") (pin "9") (pinfunction "A8_9") (pintype "bidirectional"))
    )
    (net (code "24") (name "CS_ETH") (class "Default")
      (node (ref "U$2") (pin "29") (pinfunction "PD0_29") (pintype "bidirectional"))
      (node (ref "U1") (pin "13") (pinfunction "B7_13") (pintype "bidirectional"))
    )
    (net (code "25") (name "CS_ETH_3V") (class "Default")
      (node (ref "JP2") (pin "2") (pinfunction "2_2") (pintype "passive"))
      (node (ref "U1") (pin "8") (pinfunction "A7_8") (pintype "bidirectional"))
    )
    (net (code "26") (name "D2A{slash}RF_MAX") (class "Default")
      (node (ref "RF_MAX") (pin "1") (pinfunction "1_1") (pintype "passive"))
      (node (ref "U$2") (pin "25") (pinfunction "PC7_25") (pintype "bidirectional"))
    )
    (net (code "27") (name "FREI") (class "Default")
      (node (ref "U$2") (pin "16") (pinfunction "PB2_16") (pintype "bidirectional"))
    )
    (net (code "28") (name "FREI2") (class "Default")
      (node (ref "U$2") (pin "27") (pinfunction "PB6_27") (pintype "bidirectional"))
    )
    (net (code "29") (name "FREI3") (class "Default")
      (node (ref "U$2") (pin "15") (pinfunction "PD7_15") (pintype "bidirectional"))
    )
    (net (code "30") (name "GND") (class "Default")
      (node (ref "C1") (pin "2") (pinfunction "2_2") (pintype "passive"))
      (node (ref "C11") (pin "2") (pinfunction "2_2") (pintype "passive"))
      (node (ref "C12") (pin "2") (pinfunction "2_2") (pintype "passive"))
      (node (ref "C17") (pin "-") (pinfunction "-_-") (pintype "passive"))
      (node (ref "C18") (pin "-") (pinfunction "-_-") (pintype "passive"))
      (node (ref "C2") (pin "2") (pinfunction "2_2") (pintype "passive"))
      (node (ref "C20") (pin "-") (pinfunction "-_-") (pintype "passive"))
      (node (ref "C21") (pin "-") (pinfunction "-_-") (pintype "passive"))
      (node (ref "C23") (pin "2") (pinfunction "2_2") (pintype "passive"))
      (node (ref "C24") (pin "2") (pinfunction "2_2") (pintype "passive"))
      (node (ref "C26") (pin "2") (pinfunction "2_2") (pintype "passive"))
      (node (ref "C27") (pin "2") (pinfunction "2_2") (pintype "passive"))
      (node (ref "C28") (pin "2") (pinfunction "2_2") (pintype "passive"))
      (node (ref "C3") (pin "-") (pinfunction "-_-") (pintype "passive"))
      (node (ref "C33") (pin "2") (pinfunction "2_2") (pintype "passive"))
      (node (ref "C34") (pin "2") (pinfunction "2_2") (pintype "passive"))
      (node (ref "C36") (pin "2") (pinfunction "2_2") (pintype "passive"))
      (node (ref "C37") (pin "2") (pinfunction "2_2") (pintype "passive"))
      (node (ref "C38") (pin "2") (pinfunction "2_2") (pintype "passive"))
      (node (ref "C39") (pin "2") (pinfunction "2_2") (pintype "passive"))
      (node (ref "C4") (pin "1") (pinfunction "1_1") (pintype "passive"))
      (node (ref "C40") (pin "-") (pinfunction "-_-") (pintype "passive"))
      (node (ref "C42") (pin "-") (pinfunction "-_-") (pintype "passive"))
      (node (ref "C44") (pin "2") (pinfunction "2_2") (pintype "passive"))
      (node (ref "C45") (pin "2") (pinfunction "2_2") (pintype "passive"))
      (node (ref "C5") (pin "1") (pinfunction "1_1") (pintype "passive"))
      (node (ref "C6") (pin "1") (pinfunction "1_1") (pintype "passive"))
      (node (ref "C7") (pin "1") (pinfunction "1_1") (pintype "passive"))
      (node (ref "C8") (pin "1") (pinfunction "1_1") (pintype "passive"))
      (node (ref "CF") (pin "2") (pinfunction "2_2") (pintype "passive"))
      (node (ref "CSS") (pin "2") (pinfunction "2_2") (pintype "passive"))
      (node (ref "C_DELAY") (pin "2") (pinfunction "2_2") (pintype "passive"))
      (node (ref "C_ISEN_B") (pin "2") (pinfunction "2_2") (pintype "passive"))
      (node (ref "D1") (pin "A") (pinfunction "A_A") (pintype "passive"))
      (node (ref "D14") (pin "A") (pinfunction "A_A") (pintype "passive"))
      (node (ref "D15") (pin "A") (pinfunction "A_A") (pintype "passive"))
      (node (ref "D4") (pin "A") (pinfunction "A_A") (pintype "passive"))
      (node (ref "D6") (pin "A") (pinfunction "A_A") (pintype "passive"))
      (node (ref "D7") (pin "A") (pinfunction "A_A") (pintype "passive"))
      (node (ref "IC2") (pin "3") (pinfunction "R0_3") (pintype "input"))
      (node (ref "IC2") (pin "4") (pinfunction "S0_4") (pintype "input"))
      (node (ref "IC2") (pin "6") (pinfunction "S1_6") (pintype "input"))
      (node (ref "IC2") (pin "7") (pinfunction "R1_7") (pintype "input"))
      (node (ref "IC2") (pin "8") (pinfunction "VSS_8") (pintype "power_in"))
      (node (ref "IC3") (pin "1") (pinfunction "GND_1") (pintype "input"))
      (node (ref "IC4") (pin "4") (pinfunction "V-_4") (pintype "power_in"))
      (node (ref "JP2") (pin "5") (pinfunction "5_5") (pintype "passive"))
      (node (ref "LED4") (pin "C") (pinfunction "C_C") (pintype "passive"))
      (node (ref "LED5") (pin "C") (pinfunction "C_C") (pintype "passive"))
      (node (ref "LED6") (pin "C") (pinfunction "C_C") (pintype "passive"))
      (node (ref "LED7") (pin "C") (pinfunction "C_C") (pintype "passive"))
      (node (ref "R1") (pin "1") (pinfunction "1_1") (pintype "passive"))
      (node (ref "R10") (pin "1") (pinfunction "1_1") (pintype "passive"))
      (node (ref "R13") (pin "1") (pinfunction "1_1") (pintype "passive"))
      (node (ref "R21") (pin "1") (pinfunction "1_1") (pintype "passive"))
      (node (ref "R22") (pin "1") (pinfunction "1_1") (pintype "passive"))
      (node (ref "R28") (pin "1") (pinfunction "1_1") (pintype "passive"))
      (node (ref "R51") (pin "1") (pinfunction "1_1") (pintype "passive"))
      (node (ref "R8") (pin "1") (pinfunction "1_1") (pintype "passive"))
      (node (ref "RF_MIN") (pin "1") (pinfunction "1_1") (pintype "passive"))
      (node (ref "RJ_1") (pin "P$4") (pinfunction "P$4_P$4") (pintype "bidirectional"))
      (node (ref "RJ_2") (pin "P$4") (pinfunction "P$4_P$4") (pintype "bidirectional"))
      (node (ref "R_DELAY") (pin "1") (pinfunction "1_1") (pintype "passive"))
      (node (ref "R_ISEN_B") (pin "1") (pinfunction "1_1") (pintype "passive"))
      (node (ref "SV1") (pin "10") (pinfunction "10_10") (pintype "passive"))
      (node (ref "SV1") (pin "4") (pinfunction "4_4") (pintype "passive"))
      (node (ref "SV1") (pin "6") (pinfunction "6_6") (pintype "passive"))
      (node (ref "SV1") (pin "8") (pinfunction "8_8") (pintype "passive"))
      (node (ref "T2") (pin "2") (pinfunction "E_2") (pintype "passive"))
      (node (ref "T4") (pin "2") (pinfunction "E_2") (pintype "passive"))
      (node (ref "T5") (pin "2") (pinfunction "S_2") (pintype "passive"))
      (node (ref "U$1") (pin "2") (pinfunction "VSS_2") (pintype "passive"))
      (node (ref "U$2") (pin "20") (pinfunction "AGND_20") (pintype "power_in"))
      (node (ref "U$2") (pin "5") (pinfunction "GND_5") (pintype "power_in"))
      (node (ref "U$3") (pin "10") (pinfunction "GND_10") (pintype "bidirectional"))
      (node (ref "U$3") (pin "8") (pinfunction "DIS_8") (pintype "bidirectional"))
      (node (ref "U$4") (pin "2") (pinfunction "GND_2") (pintype "bidirectional"))
      (node (ref "U$5") (pin "1") (pinfunction "NC_1") (pintype "bidirectional"))
      (node (ref "U$5") (pin "3") (pinfunction "CATHODE_3") (pintype "bidirectional"))
      (node (ref "U$5") (pin "4") (pinfunction "NC_4") (pintype "bidirectional"))
      (node (ref "U$6") (pin "1") (pinfunction "NC_1") (pintype "bidirectional"))
      (node (ref "U$6") (pin "4") (pinfunction "NC_4") (pintype "bidirectional"))
      (node (ref "U$8") (pin "3") (pinfunction "GND_3") (pintype "bidirectional"))
      (node (ref "U$8") (pin "5") (pinfunction "~{ON}/OFF_5") (pintype "bidirectional"))
      (node (ref "U1") (pin "11") (pinfunction "GND_11") (pintype "passive"))
      (node (ref "U3") (pin "6") (pinfunction "GND_6") (pintype "passive"))
      (node (ref "U4") (pin "6") (pinfunction "GND_6") (pintype "passive"))
      (node (ref "U5") (pin "11") (pinfunction "IN_1C_11") (pintype "input"))
      (node (ref "U5") (pin "13") (pinfunction "IN_3C_13") (pintype "input"))
      (node (ref "U5") (pin "5") (pinfunction "IN_3B_5") (pintype "input"))
      (node (ref "U5") (pin "7") (pinfunction "VSS_7") (pintype "passive"))
      (node (ref "U5") (pin "8") (pinfunction "IN_3A_8") (pintype "input"))
      (node (ref "X1") (pin "2") (pinfunction "KL_2") (pintype "passive"))
    )
    (net (code "31") (name "GND1") (class "Default")
      (node (ref "C10") (pin "-") (pinfunction "-_-") (pintype "passive"))
      (node (ref "C13") (pin "2") (pinfunction "2_2") (pintype "passive"))
      (node (ref "C35") (pin "2") (pinfunction "2_2") (pintype "passive"))
      (node (ref "C9") (pin "-") (pinfunction "-_-") (pintype "passive"))
      (node (ref "LED8") (pin "C") (pinfunction "C_C") (pintype "passive"))
      (node (ref "Q4") (pin "S") (pinfunction "S_S") (pintype "passive"))
      (node (ref "R31") (pin "1") (pinfunction "1_1") (pintype "passive"))
      (node (ref "R54") (pin "2") (pinfunction "2_2") (pintype "passive"))
      (node (ref "T3") (pin "2") (pinfunction "E_2") (pintype "passive"))
      (node (ref "X2") (pin "1") (pinfunction "KL_1") (pintype "passive"))
    )
    (net (code "32") (name "INT_ETH") (class "Default")
      (node (ref "U$2") (pin "30") (pinfunction "PC0_30") (pintype "bidirectional"))
      (node (ref "U1") (pin "20") (pinfunction "B1_20") (pintype "bidirectional"))
    )
    (net (code "33") (name "INT_ETH_3V") (class "Default")
      (node (ref "JP1") (pin "5") (pinfunction "5_5") (pintype "passive"))
      (node (ref "U1") (pin "1") (pinfunction "A1_1") (pintype "bidirectional"))
    )
    (net (code "34") (name "KICK") (class "Default")
      (node (ref "R19") (pin "1") (pinfunction "1_1") (pintype "passive"))
      (node (ref "U$2") (pin "23") (pinfunction "PB3_23") (pintype "bidirectional"))
    )
    (net (code "35") (name "MISO") (class "Default")
      (node (ref "U$2") (pin "8") (pinfunction "PB0_8") (pintype "bidirectional"))
      (node (ref "U1") (pin "17") (pinfunction "B3_17") (pintype "bidirectional"))
    )
    (net (code "36") (name "MISO_3V") (class "Default")
      (node (ref "JP1") (pin "3") (pinfunction "3_3") (pintype "passive"))
      (node (ref "U1") (pin "4") (pinfunction "A3_4") (pintype "bidirectional"))
    )
    (net (code "37") (name "MOSI") (class "Default")
      (node (ref "U$2") (pin "9") (pinfunction "PB1_9") (pintype "bidirectional"))
      (node (ref "U1") (pin "16") (pinfunction "B4_16") (pintype "bidirectional"))
    )
    (net (code "38") (name "MOSI_3V") (class "Default")
      (node (ref "JP1") (pin "2") (pinfunction "2_2") (pintype "passive"))
      (node (ref "U1") (pin "5") (pinfunction "A4_5") (pintype "bidirectional"))
    )
    (net (code "39") (name "NOTAUS") (class "Default")
      (node (ref "D16") (pin "K") (pinfunction "C_K") (pintype "passive"))
      (node (ref "R14") (pin "1") (pinfunction "1_1") (pintype "passive"))
      (node (ref "U$2") (pin "22") (pinfunction "PC6_22") (pintype "bidirectional"))
      (node (ref "U5") (pin "9") (pinfunction "OUTA_9") (pintype "output"))
    )
    (net (code "40") (name "Net-(COIL_IN-P)") (class "Default")
      (node (ref "COIL_IN") (pin "P$1") (pinfunction "P_P$1") (pintype "passive"))
      (node (ref "Q2") (pin "D") (pinfunction "D_D") (pintype "passive"))
      (node (ref "R20") (pin "2") (pinfunction "2_2") (pintype "passive"))
      (node (ref "U$7") (pin "A") (pinfunction "A_A") (pintype "passive"))
    )
    (net (code "41") (name "Net-(CSS-Pad1)") (class "Default")
      (node (ref "CSS") (pin "1") (pinfunction "1_1") (pintype "passive"))
      (node (ref "R_SS") (pin "1") (pinfunction "1_1") (pintype "passive"))
      (node (ref "R_SS2") (pin "1") (pinfunction "1_1") (pintype "passive"))
    )
    (net (code "42") (name "Net-(C_ISEN_A-Pad1)") (class "Default")
      (node (ref "C_ISEN_A") (pin "1") (pinfunction "1_1") (pintype "passive"))
      (node (ref "R_ISEN_A") (pin "2") (pinfunction "2_2") (pintype "passive"))
    )
    (net (code "43") (name "Net-(D3-PadA)") (class "Default")
      (node (ref "D3") (pin "A") (pinfunction "A_A") (pintype "passive"))
      (node (ref "D4") (pin "C") (pinfunction "C_C") (pintype "passive"))
      (node (ref "R_ISEN_A") (pin "1") (pinfunction "1_1") (pintype "passive"))
    )
    (net (code "44") (name "Net-(D6-C)") (class "Default")
      (node (ref "C19") (pin "2") (pinfunction "2_2") (pintype "passive"))
      (node (ref "D6") (pin "K") (pinfunction "C_K") (pintype "passive"))
      (node (ref "L5") (pin "2") (pinfunction "2_2") (pintype "passive"))
      (node (ref "U3") (pin "8") (pinfunction "VSW_8") (pintype "output"))
    )
    (net (code "45") (name "Net-(D7-C)") (class "Default")
      (node (ref "C22") (pin "2") (pinfunction "2_2") (pintype "passive"))
      (node (ref "D7") (pin "K") (pinfunction "C_K") (pintype "passive"))
      (node (ref "L6") (pin "2") (pinfunction "2_2") (pintype "passive"))
      (node (ref "U4") (pin "8") (pinfunction "VSW_8") (pintype "output"))
    )
    (net (code "46") (name "Net-(D10-C)") (class "Default")
      (node (ref "D10") (pin "K") (pinfunction "C_K") (pintype "passive"))
      (node (ref "D8") (pin "A") (pinfunction "A_A") (pintype "passive"))
      (node (ref "L7") (pin "2") (pinfunction "8_2") (pintype "passive"))
    )
    (net (code "47") (name "Net-(D11-C)") (class "Default")
      (node (ref "D11") (pin "K") (pinfunction "C_K") (pintype "passive"))
      (node (ref "D9") (pin "A") (pinfunction "A_A") (pintype "passive"))
      (node (ref "L7") (pin "4") (pinfunction "1_4") (pintype "passive"))
    )
    (net (code "48") (name "Net-(D15-C)") (class "Default")
      (node (ref "D15") (pin "K") (pinfunction "C_K") (pintype "passive"))
      (node (ref "L1") (pin "2") (pinfunction "2_2") (pintype "passive"))
      (node (ref "U$8") (pin "2") (pinfunction "VOUT_2") (pintype "bidirectional"))
    )
    (net (code "49") (name "Net-(F1-2)") (class "Default")
      (node (ref "F1") (pin "P$2") (pinfunction "2_P$2") (pintype "passive"))
      (node (ref "X1") (pin "1") (pinfunction "KL_1") (pintype "passive"))
    )
    (net (code "50") (name "Net-(IC1A-+IN)") (class "Default")
      (node (ref "C15") (pin "1") (pinfunction "1_1") (pintype "passive"))
      (node (ref "IC1") (pin "3") (pinfunction "+IN_3") (pintype "input"))
      (node (ref "IC1") (pin "5") (pinfunction "+IN_5") (pintype "input"))
      (node (ref "R101") (pin "1") (pinfunction "1_1") (pintype "passive"))
      (node (ref "R6") (pin "2") (pinfunction "2_2") (pintype "passive"))
    )
    (net (code "51") (name "Net-(IC1A--IN)") (class "Default")
      (node (ref "C14") (pin "1") (pinfunction "1_1") (pintype "passive"))
      (node (ref "IC1") (pin "2") (pinfunction "-IN_2") (pintype "input"))
      (node (ref "OK1") (pin "7") (pinfunction "EMIT_7") (pintype "passive"))
      (node (ref "R11") (pin "2") (pinfunction "2_2") (pintype "passive"))
    )
    (net (code "52") (name "Net-(IC1A-OUT)") (class "Default")
      (node (ref "IC1") (pin "1") (pinfunction "OUT_1") (pintype "output"))
      (node (ref "R105") (pin "1") (pinfunction "1_1") (pintype "passive"))
    )
    (net (code "53") (name "Net-(IC1B--IN)") (class "Default")
      (node (ref "C46") (pin "1") (pinfunction "1_1") (pintype "passive"))
      (node (ref "IC1") (pin "6") (pinfunction "-IN_6") (pintype "input"))
      (node (ref "R4") (pin "2") (pinfunction "2_2") (pintype "passive"))
      (node (ref "R7") (pin "1") (pinfunction "1_1") (pintype "passive"))
    )
    (net (code "54") (name "Net-(IC1B-OUT)") (class "Default")
      (node (ref "IC1") (pin "7") (pinfunction "OUT_7") (pintype "output"))
      (node (ref "R9") (pin "1") (pinfunction "1_1") (pintype "passive"))
    )
    (net (code "55") (name "Net-(IC2A-Q2)") (class "Default")
      (node (ref "IC2") (pin "10") (pinfunction "Q2_10") (pintype "output"))
      (node (ref "U5") (pin "1") (pinfunction "IN_1A_1") (pintype "input"))
    )
    (net (code "56") (name "Net-(IC2A-Q3)") (class "Default")
      (node (ref "IC2") (pin "1") (pinfunction "Q3_1") (pintype "output"))
      (node (ref "U5") (pin "3") (pinfunction "IN_1B_3") (pintype "input"))
    )
    (net (code "57") (name "Net-(IC4A--IN)") (class "Default")
      (node (ref "C36") (pin "1") (pinfunction "1_1") (pintype "passive"))
      (node (ref "IC4") (pin "2") (pinfunction "-IN_2") (pintype "input"))
      (node (ref "R21") (pin "2") (pinfunction "2_2") (pintype "passive"))
      (node (ref "R5") (pin "1") (pinfunction "1_1") (pintype "passive"))
      (node (ref "R52") (pin "2") (pinfunction "2_2") (pintype "passive"))
    )
    (net (code "58") (name "Net-(IC4A-OUT)") (class "Default")
      (node (ref "IC4") (pin "1") (pinfunction "OUT_1") (pintype "output"))
      (node (ref "U5") (pin "4") (pinfunction "IN_2B_4") (pintype "input"))
    )
    (net (code "59") (name "Net-(IC4B-+IN)") (class "Default")
      (node (ref "C37") (pin "1") (pinfunction "1_1") (pintype "passive"))
      (node (ref "IC4") (pin "5") (pinfunction "+IN_5") (pintype "input"))
      (node (ref "R27") (pin "1") (pinfunction "1_1") (pintype "passive"))
      (node (ref "R28") (pin "2") (pinfunction "2_2") (pintype "passive"))
    )
    (net (code "60") (name "Net-(IC4B--IN)") (class "Default")
      (node (ref "C38") (pin "1") (pinfunction "1_1") (pintype "passive"))
      (node (ref "IC4") (pin "6") (pinfunction "-IN_6") (pintype "input"))
      (node (ref "R12") (pin "1") (pinfunction "1_1") (pintype "passive"))
      (node (ref "R13") (pin "2") (pinfunction "2_2") (pintype "passive"))
    )
    (net (code "61") (name "Net-(IC4B-OUT)") (class "Default")
      (node (ref "IC4") (pin "7") (pinfunction "OUT_7") (pintype "output"))
      (node (ref "U5") (pin "12") (pinfunction "IN_2C_12") (pintype "input"))
    )
    (net (code "62") (name "Net-(L7-4)") (class "Default")
      (node (ref "L3") (pin "1") (pinfunction "1_1") (pintype "passive"))
      (node (ref "L4") (pin "1") (pinfunction "1_1") (pintype "passive"))
      (node (ref "L7") (pin "9") (pinfunction "4_9") (pintype "passive"))
    )
    (net (code "63") (name "Net-(L7-5)") (class "Default")
      (node (ref "C13") (pin "1") (pinfunction "1_1") (pintype "passive"))
      (node (ref "C_ISEN_A") (pin "2") (pinfunction "2_2") (pintype "passive"))
      (node (ref "L3") (pin "2") (pinfunction "2_2") (pintype "passive"))
      (node (ref "L7") (pin "11") (pinfunction "5_11") (pintype "passive"))
    )
    (net (code "64") (name "Net-(LED1-PadA)") (class "Default")
      (node (ref "LED1") (pin "A") (pinfunction "A_A") (pintype "passive"))
      (node (ref "R39") (pin "1") (pinfunction "1_1") (pintype "passive"))
    )
    (net (code "65") (name "Net-(LED2-PadA)") (class "Default")
      (node (ref "LED2") (pin "A") (pinfunction "A_A") (pintype "passive"))
      (node (ref "R40") (pin "1") (pinfunction "1_1") (pintype "passive"))
    )
    (net (code "66") (name "Net-(LED3-PadA)") (class "Default")
      (node (ref "LED3") (pin "A") (pinfunction "A_A") (pintype "passive"))
      (node (ref "R41") (pin "1") (pinfunction "1_1") (pintype "passive"))
    )
    (net (code "67") (name "Net-(LED4-PadA)") (class "Default")
      (node (ref "LED4") (pin "A") (pinfunction "A_A") (pintype "passive"))
      (node (ref "R42") (pin "1") (pinfunction "1_1") (pintype "passive"))
    )
    (net (code "68") (name "Net-(LED5-PadA)") (class "Default")
      (node (ref "LED5") (pin "A") (pinfunction "A_A") (pintype "passive"))
      (node (ref "R43") (pin "1") (pinfunction "1_1") (pintype "passive"))
    )
    (net (code "69") (name "Net-(LED6-PadA)") (class "Default")
      (node (ref "LED6") (pin "A") (pinfunction "A_A") (pintype "passive"))
      (node (ref "R44") (pin "1") (pinfunction "1_1") (pintype "passive"))
    )
    (net (code "70") (name "Net-(LED7-PadA)") (class "Default")
      (node (ref "LED7") (pin "A") (pinfunction "A_A") (pintype "passive"))
      (node (ref "R45") (pin "1") (pinfunction "1_1") (pintype "passive"))
    )
    (net (code "71") (name "Net-(LED8-PadA)") (class "Default")
      (node (ref "LED8") (pin "A") (pinfunction "A_A") (pintype "passive"))
      (node (ref "R46") (pin "1") (pinfunction "1_1") (pintype "passive"))
    )
    (net (code "72") (name "Net-(LED9-PadA)") (class "Default")
      (node (ref "LED9") (pin "A") (pinfunction "A_A") (pintype "passive"))
      (node (ref "R49") (pin "1") (pinfunction "1_1") (pintype "passive"))
    )
    (net (code "73") (name "Net-(LED10-PadA)") (class "Default")
      (node (ref "LED10") (pin "A") (pinfunction "A_A") (pintype "passive"))
      (node (ref "R50") (pin "1") (pinfunction "1_1") (pintype "passive"))
    )
    (net (code "74") (name "Net-(OK1A-A)") (class "Default")
      (node (ref "OK1") (pin "1") (pinfunction "A_1") (pintype "passive"))
      (node (ref "R105") (pin "2") (pinfunction "2_2") (pintype "passive"))
    )
    (net (code "75") (name "Net-(OK1A-C)") (class "Default")
      (node (ref "OK1") (pin "2") (pinfunction "C_2") (pintype "passive"))
      (node (ref "OK1") (pin "3") (pinfunction "A_3") (pintype "passive"))
    )
    (net (code "76") (name "Net-(OK2A-A)") (class "Default")
      (node (ref "OK2") (pin "1") (pinfunction "A_1") (pintype "passive"))
      (node (ref "R9") (pin "2") (pinfunction "2_2") (pintype "passive"))
    )
    (net (code "77") (name "Net-(Q2-PadG)") (class "Default")
      (node (ref "Q2") (pin "G") (pinfunction "G_G") (pintype "passive"))
      (node (ref "R18") (pin "2") (pinfunction "2_2") (pintype "passive"))
    )
    (net (code "78") (name "Net-(Q5-D)") (class "Default")
      (node (ref "C10") (pin "+") (pinfunction "+_+") (pintype "passive"))
      (node (ref "C35") (pin "1") (pinfunction "1_1") (pintype "passive"))
      (node (ref "C9") (pin "+") (pinfunction "+_+") (pintype "passive"))
      (node (ref "Q3") (pin "D") (pinfunction "D_D") (pintype "passive"))
      (node (ref "Q5") (pin "4") (pinfunction "D_4") (pintype "passive"))
      (node (ref "R23") (pin "2") (pinfunction "2_2") (pintype "passive"))
    )
    (net (code "79") (name "Net-(Q5-G)") (class "Default")
      (node (ref "D13") (pin "C") (pinfunction "C_C") (pintype "passive"))
      (node (ref "Q5") (pin "1") (pinfunction "G_1") (pintype "passive"))
      (node (ref "R200") (pin "1") (pinfunction "1_1") (pintype "passive"))
    )
    (net (code "80") (name "Net-(Q6-PadD)") (class "Default")
      (node (ref "Q6") (pin "D") (pinfunction "D_D") (pintype "passive"))
      (node (ref "R3") (pin "2") (pinfunction "2_2") (pintype "passive"))
    )
    (net (code "81") (name "Net-(R2-Pad2)") (class "Default")
      (node (ref "R2") (pin "2") (pinfunction "2_2") (pintype "passive"))
      (node (ref "R3") (pin "1") (pinfunction "1_1") (pintype "passive"))
    )
    (net (code "82") (name "Net-(R15-Pad1)") (class "Default")
      (node (ref "R15") (pin "1") (pinfunction "1_1") (pintype "passive"))
      (node (ref "U$5") (pin "6") (pinfunction "VO_6") (pintype "bidirectional"))
      (node (ref "U$5") (pin "7") (pinfunction "VO_7") (pintype "bidirectional"))
    )
    (net (code "83") (name "Net-(R18-Pad1)") (class "Default")
      (node (ref "R18") (pin "1") (pinfunction "1_1") (pintype "passive"))
      (node (ref "U$6") (pin "6") (pinfunction "VO_6") (pintype "bidirectional"))
      (node (ref "U$6") (pin "7") (pinfunction "VO_7") (pintype "bidirectional"))
    )
    (net (code "84") (name "Net-(R32-Pad1)") (class "Default")
      (node (ref "R32") (pin "1") (pinfunction "1_1") (pintype "passive"))
      (node (ref "SJ1") (pin "1") (pinfunction "1_1") (pintype "passive"))
    )
    (net (code "85") (name "Net-(T1-B)") (class "Default")
      (node (ref "R15") (pin "2") (pinfunction "2_2") (pintype "passive"))
      (node (ref "T1") (pin "1") (pinfunction "B_1") (pintype "passive"))
    )
    (net (code "86") (name "Net-(T1-C)") (class "Default")
      (node (ref "D5") (pin "C") (pinfunction "C_C") (pintype "passive"))
      (node (ref "Q6") (pin "G") (pinfunction "G_G") (pintype "passive"))
      (node (ref "R16") (pin "1") (pinfunction "1_1") (pintype "passive"))
      (node (ref "T1") (pin "3") (pinfunction "C_3") (pintype "passive"))
    )
    (net (code "87") (name "Net-(T2-B)") (class "Default")
      (node (ref "R19") (pin "2") (pinfunction "2_2") (pintype "passive"))
      (node (ref "R51") (pin "2") (pinfunction "2_2") (pintype "passive"))
      (node (ref "T2") (pin "1") (pinfunction "B_1") (pintype "passive"))
    )
    (net (code "88") (name "Net-(T2-C)") (class "Default")
      (node (ref "T2") (pin "3") (pinfunction "C_3") (pintype "passive"))
      (node (ref "U$6") (pin "3") (pinfunction "CATHODE_3") (pintype "bidirectional"))
    )
    (net (code "89") (name "Net-(T3-B)") (class "Default")
      (node (ref "R24") (pin "2") (pinfunction "2_2") (pintype "passive"))
      (node (ref "T3") (pin "1") (pinfunction "B_1") (pintype "passive"))
    )
    (net (code "90") (name "Net-(T3-C)") (class "Default")
      (node (ref "D13") (pin "A") (pinfunction "A_A") (pintype "passive"))
      (node (ref "T3") (pin "3") (pinfunction "C_3") (pintype "passive"))
    )
    (net (code "91") (name "Net-(T4-B)") (class "Default")
      (node (ref "R25") (pin "2") (pinfunction "2_2") (pintype "passive"))
      (node (ref "T4") (pin "1") (pinfunction "B_1") (pintype "passive"))
    )
    (net (code "92") (name "Net-(T4-C)") (class "Default")
      (node (ref "R26") (pin "1") (pinfunction "1_1") (pintype "passive"))
      (node (ref "T4") (pin "3") (pinfunction "C_3") (pintype "passive"))
      (node (ref "U5") (pin "2") (pinfunction "IN_2A_2") (pintype "input"))
    )
    (net (code "93") (name "Net-(T5-D)") (class "Default")
      (node (ref "JP3") (pin "3") (pinfunction "3_3") (pintype "passive"))
      (node (ref "T5") (pin "1") (pinfunction "D_1") (pintype "passive"))
    )
    (net (code "94") (name "Net-(T5-G)") (class "Default")
      (node (ref "R47") (pin "2") (pinfunction "2_2") (pintype "passive"))
      (node (ref "T5") (pin "3") (pinfunction "G_3") (pintype "passive"))
    )
    (net (code "95") (name "Net-(U$1-RS)") (class "Default")
      (node (ref "R1") (pin "2") (pinfunction "2_2") (pintype "passive"))
      (node (ref "U$1") (pin "8") (pinfunction "RS_8") (pintype "input"))
    )
    (net (code "96") (name "Net-(U$2-AREF)") (class "Default")
      (node (ref "C6") (pin "2") (pinfunction "2_2") (pintype "passive"))
      (node (ref "U$2") (pin "21") (pinfunction "AREF_21") (pintype "bidirectional"))
    )
    (net (code "97") (name "Net-(U$2-PE1(XTAL1))") (class "Default")
      (node (ref "C5") (pin "2") (pinfunction "2_2") (pintype "passive"))
      (node (ref "Q1") (pin "1") (pinfunction "1_1") (pintype "passive"))
      (node (ref "U$2") (pin "10") (pinfunction "PE1(XTAL1)_10") (pintype "bidirectional"))
    )
    (net (code "98") (name "Net-(U$2-PE2(XTAL2))") (class "Default")
      (node (ref "C4") (pin "2") (pinfunction "2_2") (pintype "passive"))
      (node (ref "Q1") (pin "2") (pinfunction "2_2") (pintype "passive"))
      (node (ref "U$2") (pin "11") (pinfunction "PE2(XTAL2)_11") (pintype "bidirectional"))
    )
    (net (code "99") (name "Net-(U$3-CF)") (class "Default")
      (node (ref "CF") (pin "1") (pinfunction "1_1") (pintype "passive"))
      (node (ref "U$3") (pin "3") (pinfunction "CF_3") (pintype "bidirectional"))
    )
    (net (code "100") (name "Net-(U$3-CSS)") (class "Default")
      (node (ref "R_SS2") (pin "2") (pinfunction "2_2") (pintype "passive"))
      (node (ref "U$3") (pin "1") (pinfunction "CSS_1") (pintype "bidirectional"))
    )
    (net (code "101") (name "Net-(U$3-DELAY)") (class "Default")
      (node (ref "C_DELAY") (pin "1") (pinfunction "1_1") (pintype "passive"))
      (node (ref "R_DELAY") (pin "2") (pinfunction "2_2") (pintype "passive"))
      (node (ref "U$3") (pin "2") (pinfunction "DELAY_2") (pintype "bidirectional"))
    )
    (net (code "102") (name "Net-(U$3-HVG)") (class "Default")
      (node (ref "Q3") (pin "G") (pinfunction "G_G") (pintype "passive"))
      (node (ref "R53") (pin "1") (pinfunction "1_1") (pintype "passive"))
      (node (ref "U$3") (pin "15") (pinfunction "HVG_15") (pintype "bidirectional"))
    )
    (net (code "103") (name "Net-(U$3-ISEN)") (class "Default")
      (node (ref "C_ISEN_B") (pin "1") (pinfunction "1_1") (pintype "passive"))
      (node (ref "D3") (pin "C") (pinfunction "C_C") (pintype "passive"))
      (node (ref "R_ISEN_B") (pin "2") (pinfunction "2_2") (pintype "passive"))
      (node (ref "U$3") (pin "6") (pinfunction "ISEN_6") (pintype "bidirectional"))
    )
    (net (code "104") (name "Net-(U$3-LINE)") (class "Default")
      (node (ref "R_LINE") (pin "2") (pinfunction "2_2") (pintype "passive"))
      (node (ref "U$3") (pin "7") (pinfunction "LINE_7") (pintype "bidirectional"))
    )
    (net (code "105") (name "Net-(U$3-LVG)") (class "Default")
      (node (ref "Q4") (pin "G") (pinfunction "G_G") (pintype "passive"))
      (node (ref "R54") (pin "1") (pinfunction "1_1") (pintype "passive"))
      (node (ref "U$3") (pin "11") (pinfunction "LVG_11") (pintype "bidirectional"))
    )
    (net (code "106") (name "Net-(U$3-OUT)") (class "Default")
      (node (ref "C_BOOT") (pin "2") (pinfunction "2_2") (pintype "passive"))
      (node (ref "L4") (pin "2") (pinfunction "2_2") (pintype "passive"))
      (node (ref "Q3") (pin "S") (pinfunction "S_S") (pintype "passive"))
      (node (ref "Q4") (pin "D") (pinfunction "D_D") (pintype "passive"))
      (node (ref "R53") (pin "2") (pinfunction "2_2") (pintype "passive"))
      (node (ref "U$3") (pin "14") (pinfunction "OUT_14") (pintype "bidirectional"))
    )
    (net (code "107") (name "Net-(U$3-RFMIN)") (class "Default")
      (node (ref "RF_MAX") (pin "2") (pinfunction "2_2") (pintype "passive"))
      (node (ref "RF_MIN") (pin "2") (pinfunction "2_2") (pintype "passive"))
      (node (ref "R_SS") (pin "2") (pinfunction "2_2") (pintype "passive"))
      (node (ref "U$3") (pin "4") (pinfunction "RFMIN_4") (pintype "bidirectional"))
    )
    (net (code "108") (name "Net-(U$3-VBOOT)") (class "Default")
      (node (ref "C_BOOT") (pin "1") (pinfunction "1_1") (pintype "passive"))
      (node (ref "U$3") (pin "16") (pinfunction "VBOOT_16") (pintype "bidirectional"))
    )
    (net (code "109") (name "Net-(U$5-ANODE)") (class "Default")
      (node (ref "R14") (pin "2") (pinfunction "2_2") (pintype "passive"))
      (node (ref "U$5") (pin "2") (pinfunction "ANODE_2") (pintype "bidirectional"))
    )
    (net (code "110") (name "Net-(U$6-ANODE)") (class "Default")
      (node (ref "R17") (pin "1") (pinfunction "1_1") (pintype "passive"))
      (node (ref "U$6") (pin "2") (pinfunction "ANODE_2") (pintype "bidirectional"))
    )
    (net (code "111") (name "Net-(U3-CB)") (class "Default")
      (node (ref "C19") (pin "1") (pinfunction "1_1") (pintype "passive"))
      (node (ref "U3") (pin "1") (pinfunction "CB_1") (pintype "input"))
    )
    (net (code "112") (name "Net-(U4-CB)") (class "Default")
      (node (ref "C22") (pin "1") (pinfunction "1_1") (pintype "passive"))
      (node (ref "U4") (pin "1") (pinfunction "CB_1") (pintype "input"))
    )
    (net (code "113") (name "Net-(VR1-C)") (class "Default")
      (node (ref "LED1") (pin "C") (pinfunction "C_C") (pintype "passive"))
      (node (ref "VR1") (pin "1") (pinfunction "C_1") (pintype "passive"))
    )
    (net (code "114") (name "Net-(VR1-R)") (class "Default")
      (node (ref "R33") (pin "1") (pinfunction "1_1") (pintype "passive"))
      (node (ref "R36") (pin "2") (pinfunction "2_2") (pintype "passive"))
      (node (ref "VR1") (pin "2") (pinfunction "R_2") (pintype "passive"))
    )
    (net (code "115") (name "Net-(VR2-C)") (class "Default")
      (node (ref "LED2") (pin "C") (pinfunction "C_C") (pintype "passive"))
      (node (ref "VR2") (pin "1") (pinfunction "C_1") (pintype "passive"))
    )
    (net (code "116") (name "Net-(VR2-R)") (class "Default")
      (node (ref "R34") (pin "1") (pinfunction "1_1") (pintype "passive"))
      (node (ref "R37") (pin "2") (pinfunction "2_2") (pintype "passive"))
      (node (ref "VR2") (pin "2") (pinfunction "R_2") (pintype "passive"))
    )
    (net (code "117") (name "Net-(VR3-C)") (class "Default")
      (node (ref "LED3") (pin "C") (pinfunction "C_C") (pintype "passive"))
      (node (ref "VR3") (pin "1") (pinfunction "C_1") (pintype "passive"))
    )
    (net (code "118") (name "Net-(VR3-R)") (class "Default")
      (node (ref "R35") (pin "1") (pinfunction "1_1") (pintype "passive"))
      (node (ref "R38") (pin "2") (pinfunction "2_2") (pintype "passive"))
      (node (ref "VR3") (pin "2") (pinfunction "R_2") (pintype "passive"))
    )
    (net (code "119") (name "OC0A{slash}MOSI_A") (class "Default")
      (node (ref "SV1") (pin "1") (pinfunction "1_1") (pintype "passive"))
    )
    (net (code "120") (name "OC0A{slash}MOSI_A{slash}KICK_VOLTAGE") (class "Default")
      (node (ref "R52") (pin "1") (pinfunction "1_1") (pintype "passive"))
      (node (ref "U$2") (pin "2") (pinfunction "(MOSI_A/TXD)PD3_2") (pintype "bidirectional"))
    )
    (net (code "121") (name "OC1A{slash}MISO_A") (class "Default")
      (node (ref "SV1") (pin "9") (pinfunction "9_9") (pintype "passive"))
      (node (ref "U$2") (pin "1") (pinfunction "(MISO_A)PD2_1") (pintype "bidirectional"))
    )
    (net (code "122") (name "RESET_NOTAUS") (class "Default")
      (node (ref "IC2") (pin "11") (pinfunction "R2_11") (pintype "input"))
      (node (ref "IC2") (pin "15") (pinfunction "R3_15") (pintype "input"))
      (node (ref "U$2") (pin "24") (pinfunction "PB4_24") (pintype "bidirectional"))
    )
    (net (code "123") (name "RST") (class "Default")
      (node (ref "SV1") (pin "5") (pinfunction "5_5") (pintype "passive"))
      (node (ref "U$2") (pin "31") (pinfunction "PE0(RESET)_31") (pintype "input"))
    )
    (net (code "124") (name "RST_ETH") (class "Default")
      (node (ref "U$2") (pin "32") (pinfunction "PD1_32") (pintype "bidirectional"))
      (node (ref "U1") (pin "14") (pinfunction "B6_14") (pintype "bidirectional"))
    )
    (net (code "125") (name "RST_ETH_3V") (class "Default")
      (node (ref "JP2") (pin "3") (pinfunction "3_3") (pintype "passive"))
      (node (ref "U1") (pin "7") (pinfunction "A6_7") (pintype "bidirectional"))
    )
    (net (code "126") (name "SCK") (class "Default")
      (node (ref "U$2") (pin "28") (pinfunction "(SCK)PB7_28") (pintype "bidirectional"))
      (node (ref "U1") (pin "15") (pinfunction "B5_15") (pintype "bidirectional"))
    )
    (net (code "127") (name "SCK_3V") (class "Default")
      (node (ref "JP1") (pin "1") (pinfunction "1_1") (pintype "passive"))
      (node (ref "U1") (pin "6") (pinfunction "A5_6") (pintype "bidirectional"))
    )
    (net (code "128") (name "SERVO_PWM") (class "Default")
      (node (ref "JP3") (pin "1") (pinfunction "1_1") (pintype "passive"))
      (node (ref "U$2") (pin "3") (pinfunction "PC1_3") (pintype "bidirectional"))
    )
    (net (code "129") (name "STBY") (class "Default")
      (node (ref "C12") (pin "1") (pinfunction "1_1") (pintype "passive"))
      (node (ref "D16") (pin "A") (pinfunction "A_A") (pintype "passive"))
      (node (ref "D17") (pin "A") (pinfunction "A_A") (pintype "passive"))
      (node (ref "R48") (pin "1") (pinfunction "1_1") (pintype "passive"))
      (node (ref "U$2") (pin "17") (pinfunction "PC4_17") (pintype "bidirectional"))
      (node (ref "U$3") (pin "5") (pinfunction "STBY_5") (pintype "bidirectional"))
    )
    (net (code "130") (name "TASTER") (class "Default")
      (node (ref "C33") (pin "1") (pinfunction "1_1") (pintype "passive"))
      (node (ref "IC2") (pin "14") (pinfunction "S3_14") (pintype "input"))
      (node (ref "R22") (pin "2") (pinfunction "2_2") (pintype "passive"))
      (node (ref "S1") (pin "3") (pinfunction "P_3") (pintype "passive"))
      (node (ref "S1") (pin "4") (pinfunction "P1_4") (pintype "passive"))
    )
    (net (code "131") (name "WOL_ETH") (class "Default")
      (node (ref "U1") (pin "18") (pinfunction "B2_18") (pintype "bidirectional"))
    )
    (net (code "132") (name "WOL_ETH_3V") (class "Default")
      (node (ref "JP1") (pin "4") (pinfunction "4_4") (pintype "passive"))
      (node (ref "U1") (pin "3") (pinfunction "A2_3") (pintype "bidirectional"))
    )
    (net (code "133") (name "unconnected-(H1-MOUNT-PadB3,0)") (class "Default")
      (node (ref "H1") (pin "B3,0") (pinfunction "MOUNT_B3,0") (pintype "passive"))
    )
    (net (code "134") (name "unconnected-(H2-MOUNT-PadB3,0)") (class "Default")
      (node (ref "H2") (pin "B3,0") (pinfunction "MOUNT_B3,0") (pintype "passive"))
    )
    (net (code "135") (name "unconnected-(H3-MOUNT-PadB3,0)") (class "Default")
      (node (ref "H3") (pin "B3,0") (pinfunction "MOUNT_B3,0") (pintype "passive"))
    )
    (net (code "136") (name "unconnected-(H4-MOUNT-PadB3,0)") (class "Default")
      (node (ref "H4") (pin "B3,0") (pinfunction "MOUNT_B3,0") (pintype "passive"))
    )
    (net (code "137") (name "unconnected-(IC2A-EN-Pad5)") (class "Default")
      (node (ref "IC2") (pin "5") (pinfunction "EN_5") (pintype "input"))
    )
    (net (code "138") (name "unconnected-(IC2A-Q0-Pad2)") (class "Default")
      (node (ref "IC2") (pin "2") (pinfunction "Q0_2") (pintype "output"))
    )
    (net (code "139") (name "unconnected-(IC2A-Q1-Pad9)") (class "Default")
      (node (ref "IC2") (pin "9") (pinfunction "Q1_9") (pintype "output"))
    )
    (net (code "140") (name "unconnected-(L7-2-Pad8)") (class "Default")
      (node (ref "L7") (pin "8") (pinfunction "2_8") (pintype "passive"))
    )
    (net (code "141") (name "unconnected-(L7-3-Pad10)") (class "Default")
      (node (ref "L7") (pin "10") (pinfunction "3_10") (pintype "passive"))
    )
    (net (code "142") (name "unconnected-(L7-7-Pad5)") (class "Default")
      (node (ref "L7") (pin "5") (pinfunction "7_5") (pintype "passive"))
    )
    (net (code "143") (name "unconnected-(L7-Pad6)") (class "Default")
      (node (ref "L7") (pin "6") (pinfunction "6_6") (pintype "passive"))
    )
    (net (code "144") (name "unconnected-(OK2B-A-Pad3)") (class "Default")
      (node (ref "OK2") (pin "3") (pinfunction "A_3") (pintype "passive"))
    )
    (net (code "145") (name "unconnected-(OK2B-C-Pad4)") (class "Default")
      (node (ref "OK2") (pin "4") (pinfunction "C_4") (pintype "passive"))
    )
    (net (code "146") (name "unconnected-(OK2B-COL-Pad6)") (class "Default")
      (node (ref "OK2") (pin "6") (pinfunction "COL_6") (pintype "passive"))
    )
    (net (code "147") (name "unconnected-(OK2B-EMIT-Pad5)") (class "Default")
      (node (ref "OK2") (pin "5") (pinfunction "EMIT_5") (pintype "passive"))
    )
    (net (code "148") (name "unconnected-(RJ_1-PadP$1)") (class "Default")
      (node (ref "RJ_1") (pin "P$1") (pinfunction "P$1_P$1") (pintype "bidirectional"))
    )
    (net (code "149") (name "unconnected-(RJ_2-PadP$1)") (class "Default")
      (node (ref "RJ_2") (pin "P$1") (pinfunction "P$1_P$1") (pintype "bidirectional"))
    )
    (net (code "150") (name "unconnected-(SV1-Pad3)") (class "Default")
      (node (ref "SV1") (pin "3") (pinfunction "3_3") (pintype "passive"))
    )
    (net (code "151") (name "unconnected-(U$1-VREF-Pad5)") (class "Default")
      (node (ref "U$1") (pin "5") (pinfunction "VREF_5") (pintype "output"))
    )
    (net (code "152") (name "unconnected-(U$3-NC-Pad13)") (class "Default")
      (node (ref "U$3") (pin "13") (pinfunction "NC_13") (pintype "bidirectional"))
    )
    (net (code "153") (name "unconnected-(U$3-PFC_STOP-Pad9)") (class "Default")
      (node (ref "U$3") (pin "9") (pinfunction "PFC_STOP_9") (pintype "bidirectional"))
    )
    (net (code "154") (name "unconnected-(U3-NC-Pad3)") (class "Default")
      (node (ref "U3") (pin "3") (pinfunction "NC_3") (pintype "no_connect"))
    )
    (net (code "155") (name "unconnected-(U3-NC_2-Pad2)") (class "Default")
      (node (ref "U3") (pin "2") (pinfunction "NC_2_2") (pintype "no_connect"))
    )
    (net (code "156") (name "unconnected-(U3-ON{slash}~{OFF}-Pad5)") (class "Default")
      (node (ref "U3") (pin "5") (pinfunction "ON/~{OFF}_5") (pintype "input"))
    )
    (net (code "157") (name "unconnected-(U4-NC-Pad3)") (class "Default")
      (node (ref "U4") (pin "3") (pinfunction "NC_3") (pintype "no_connect"))
    )
    (net (code "158") (name "unconnected-(U4-NC_2-Pad2)") (class "Default")
      (node (ref "U4") (pin "2") (pinfunction "NC_2_2") (pintype "no_connect"))
    )
    (net (code "159") (name "unconnected-(U4-ON{slash}~{OFF}-Pad5)") (class "Default")
      (node (ref "U4") (pin "5") (pinfunction "ON/~{OFF}_5") (pintype "input"))
    )
    (net (code "160") (name "unconnected-(U5-OUTC-Pad10)") (class "Default")
      (node (ref "U5") (pin "10") (pinfunction "OUTC_10") (pintype "output"))
    )
    (net (code "161") (name "ÜBERSPANNUNG") (class "Default")
      (node (ref "C24") (pin "1") (pinfunction "1_1") (pintype "passive"))
      (node (ref "IC2") (pin "12") (pinfunction "S2_12") (pintype "input"))
      (node (ref "OK2") (pin "7") (pinfunction "EMIT_7") (pintype "passive"))
      (node (ref "R10") (pin "2") (pinfunction "2_2") (pintype "passive"))
    )
  )
)
